# NeuroStimDuino_v2.net
KiCad netlist of a schematic drawn in EAGLE
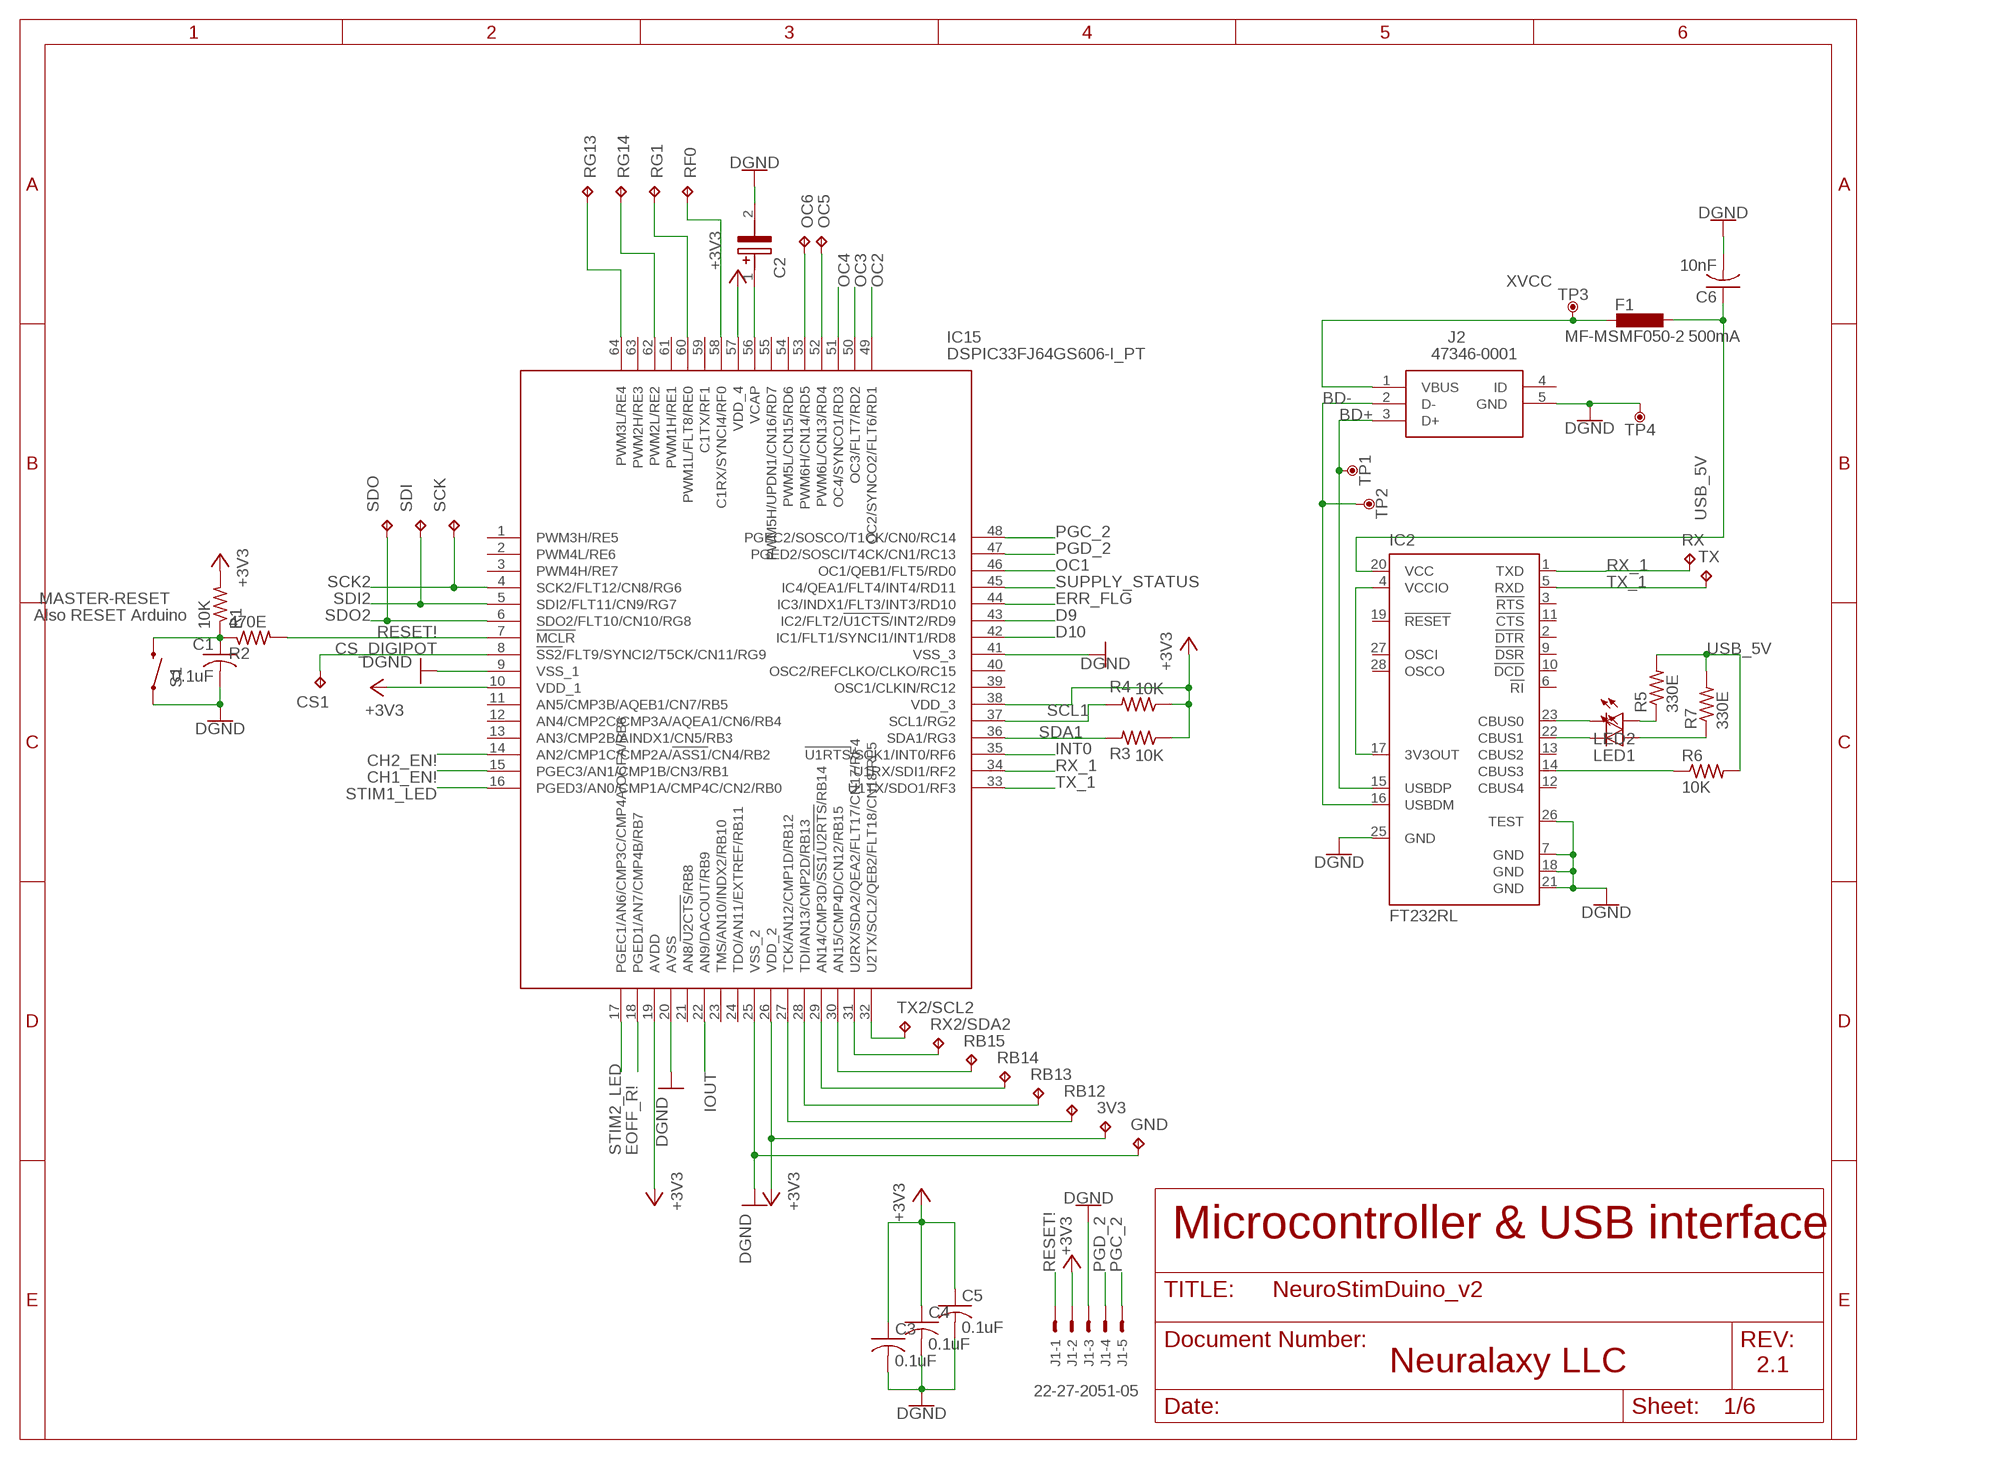
[diagram p0: schematic, sheet 1]
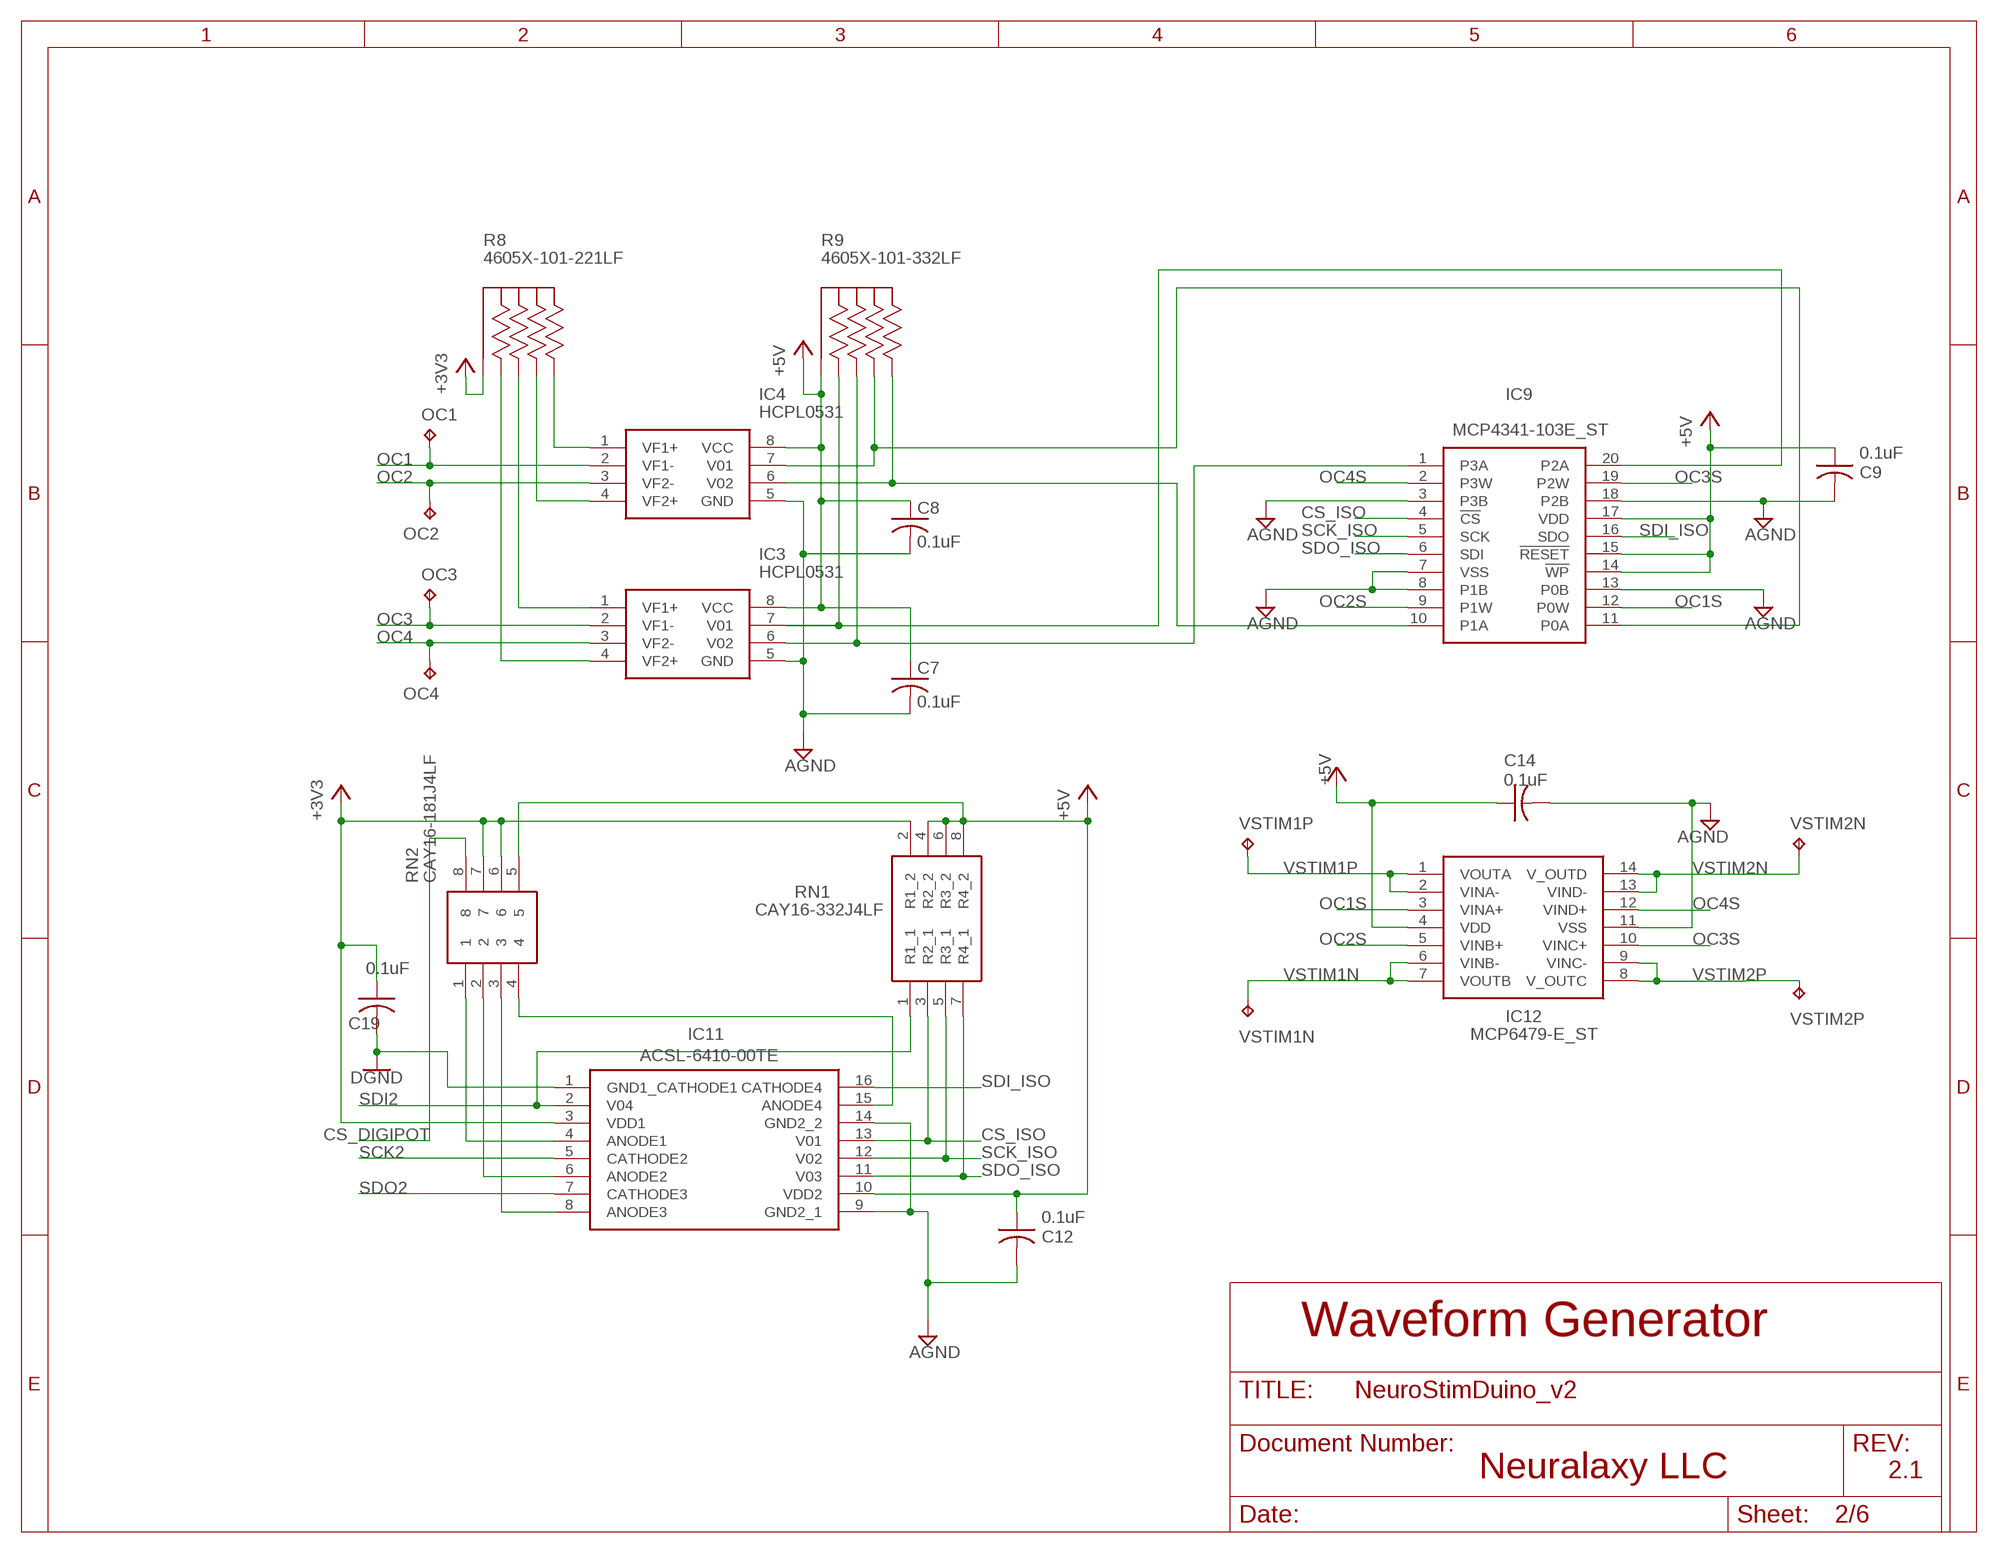
[diagram p1: schematic, sheet 2]
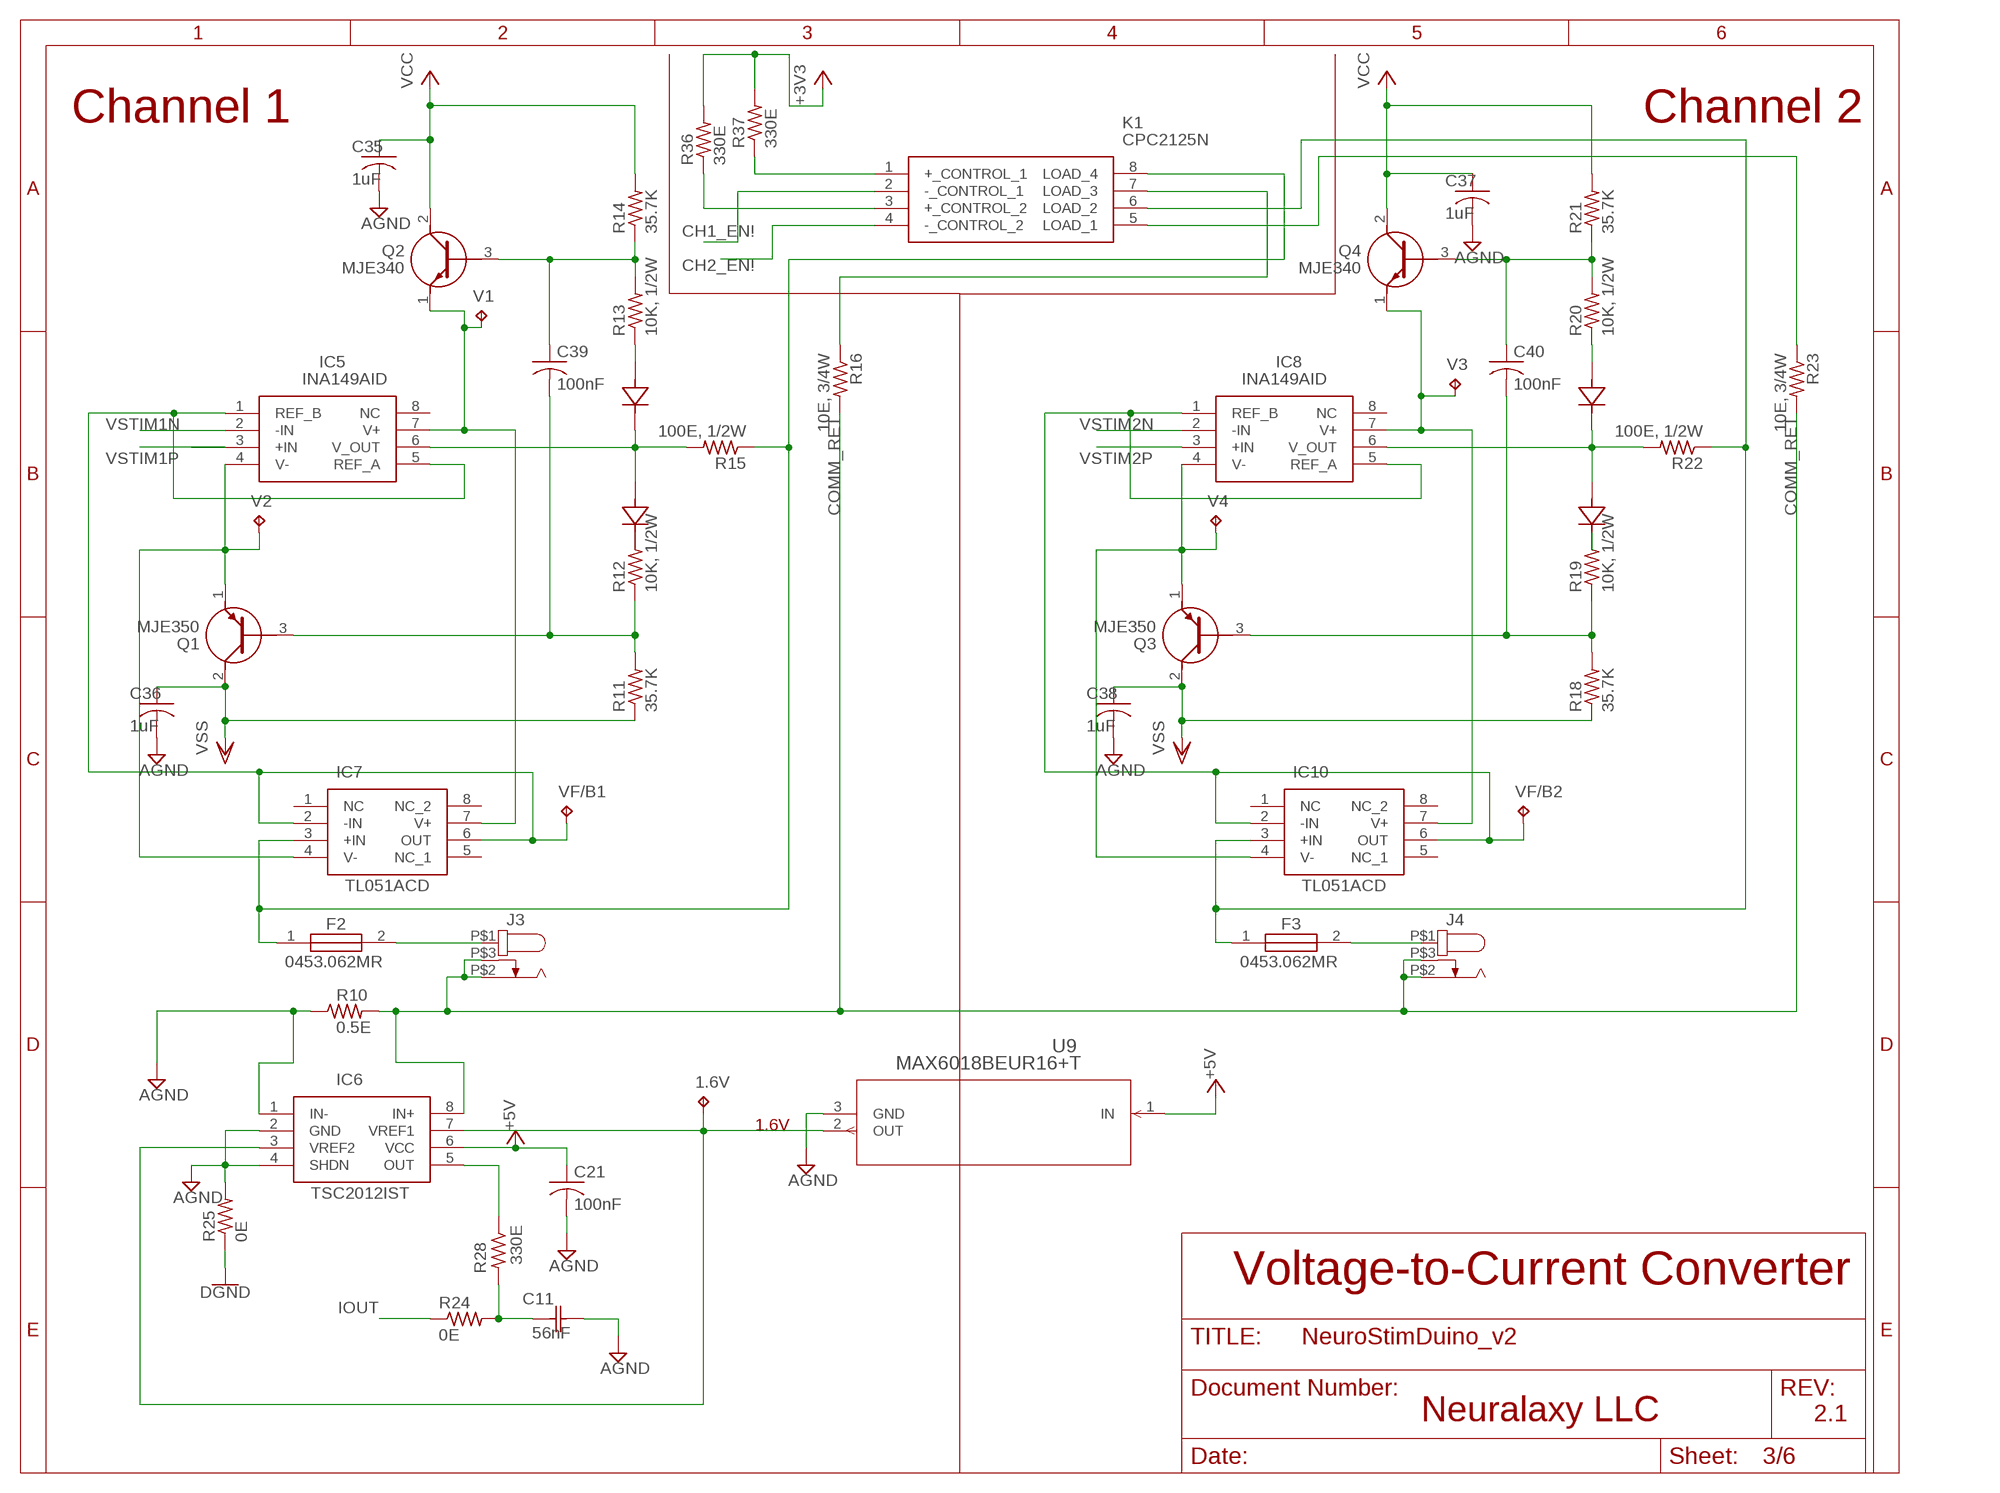
[diagram p2: schematic, sheet 3]
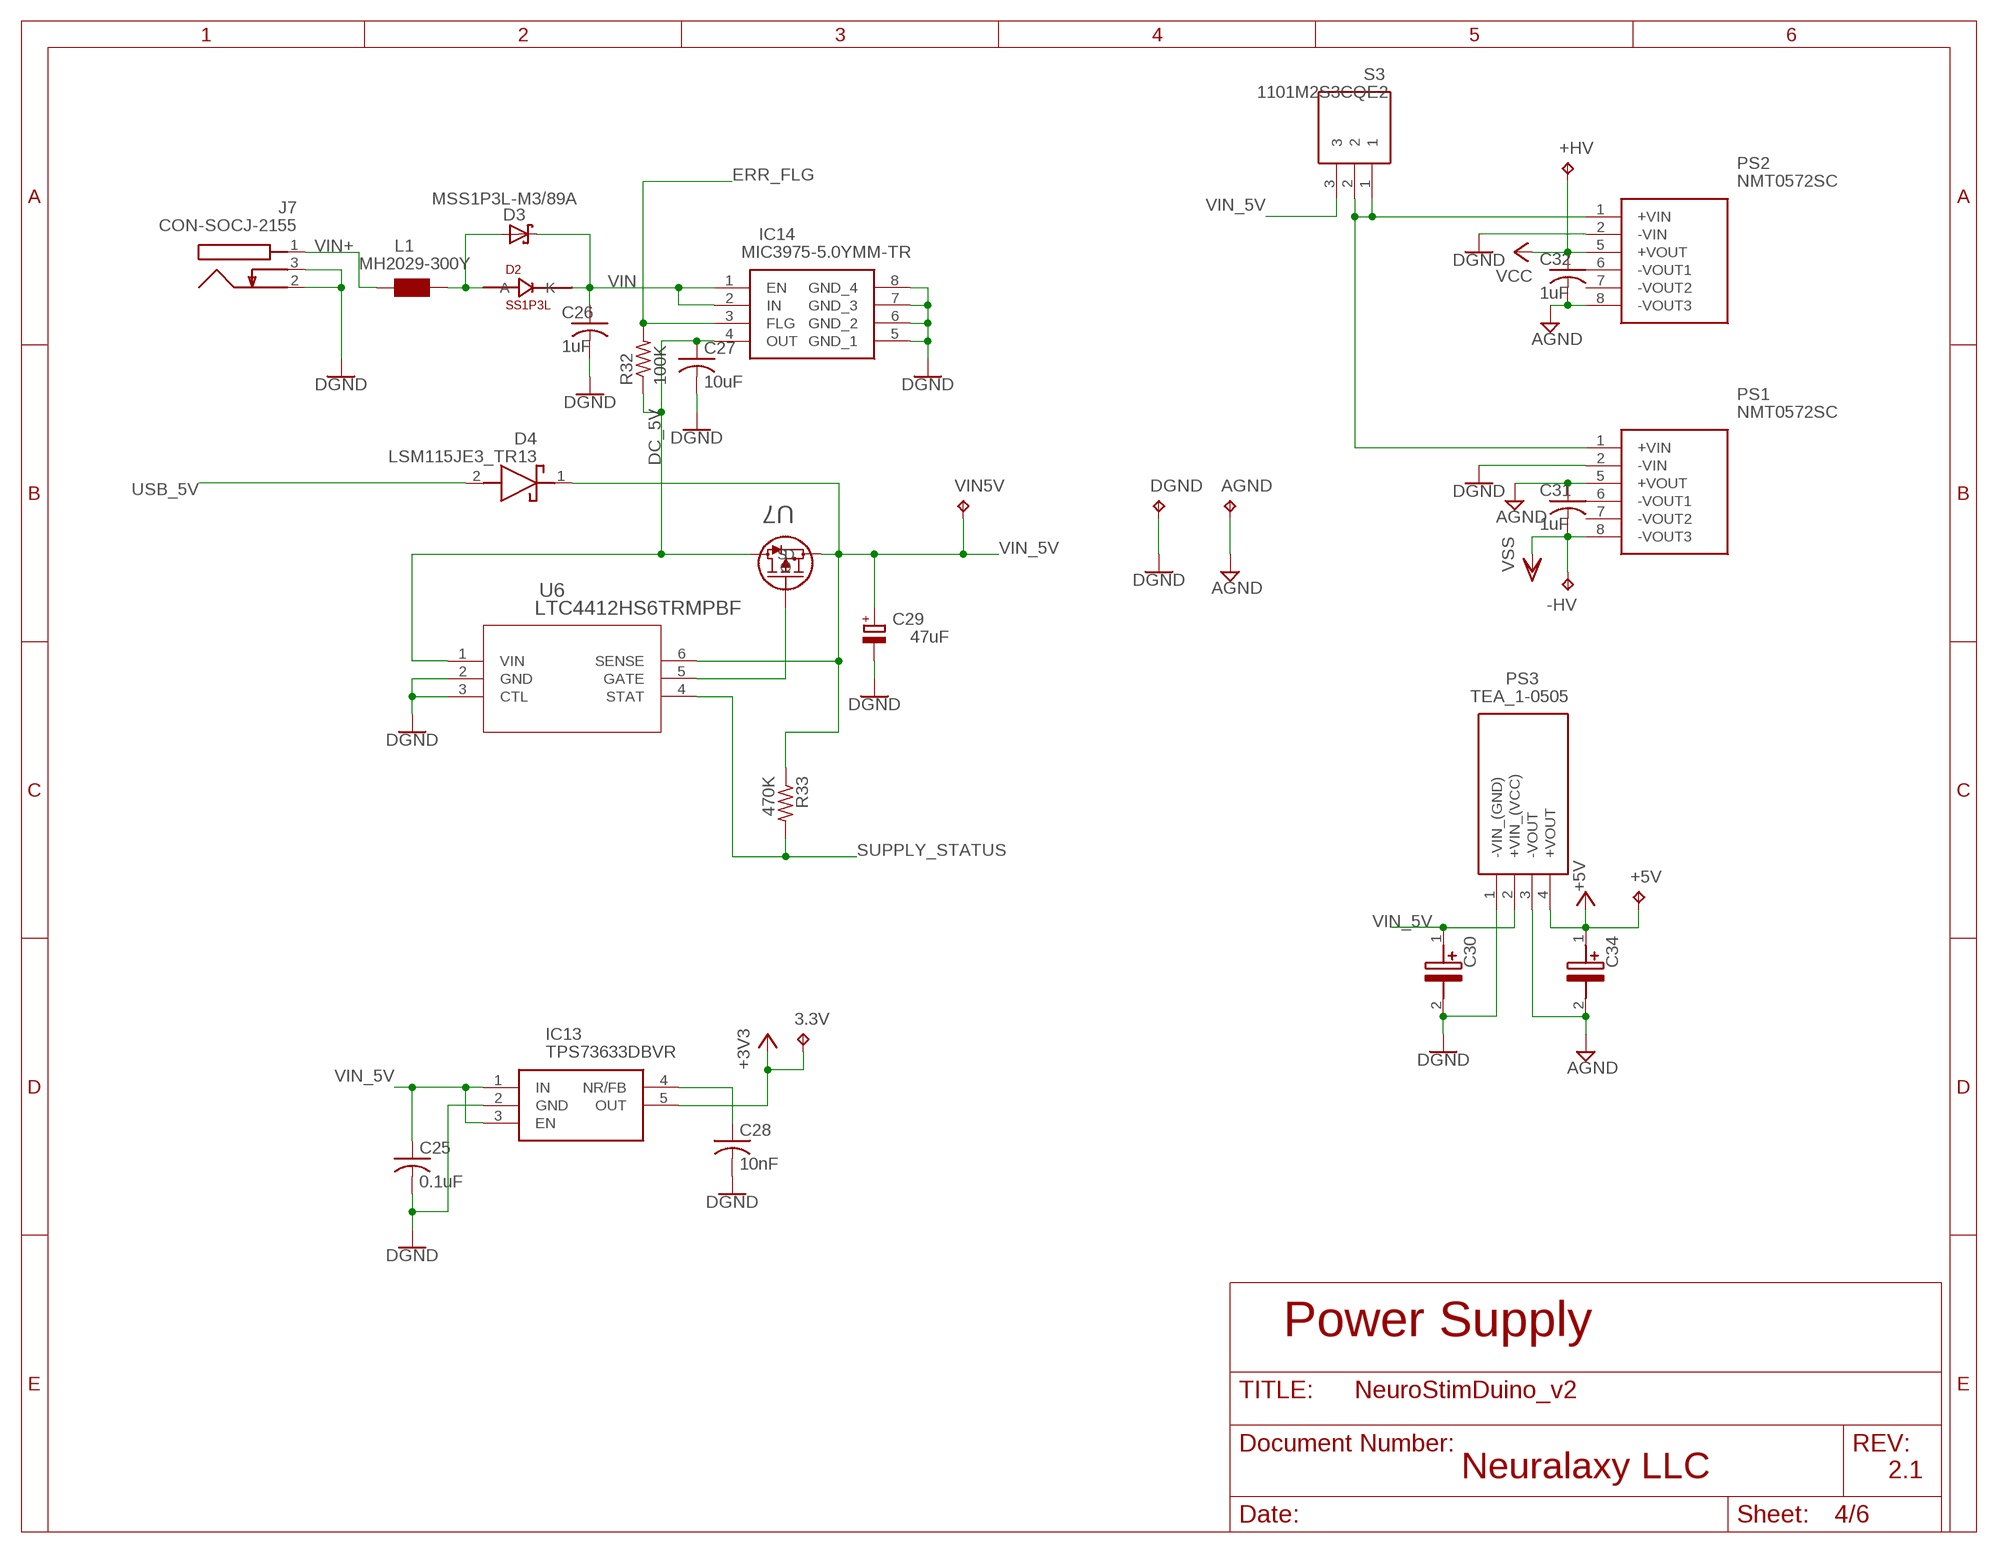
[diagram p3: schematic, sheet 4]
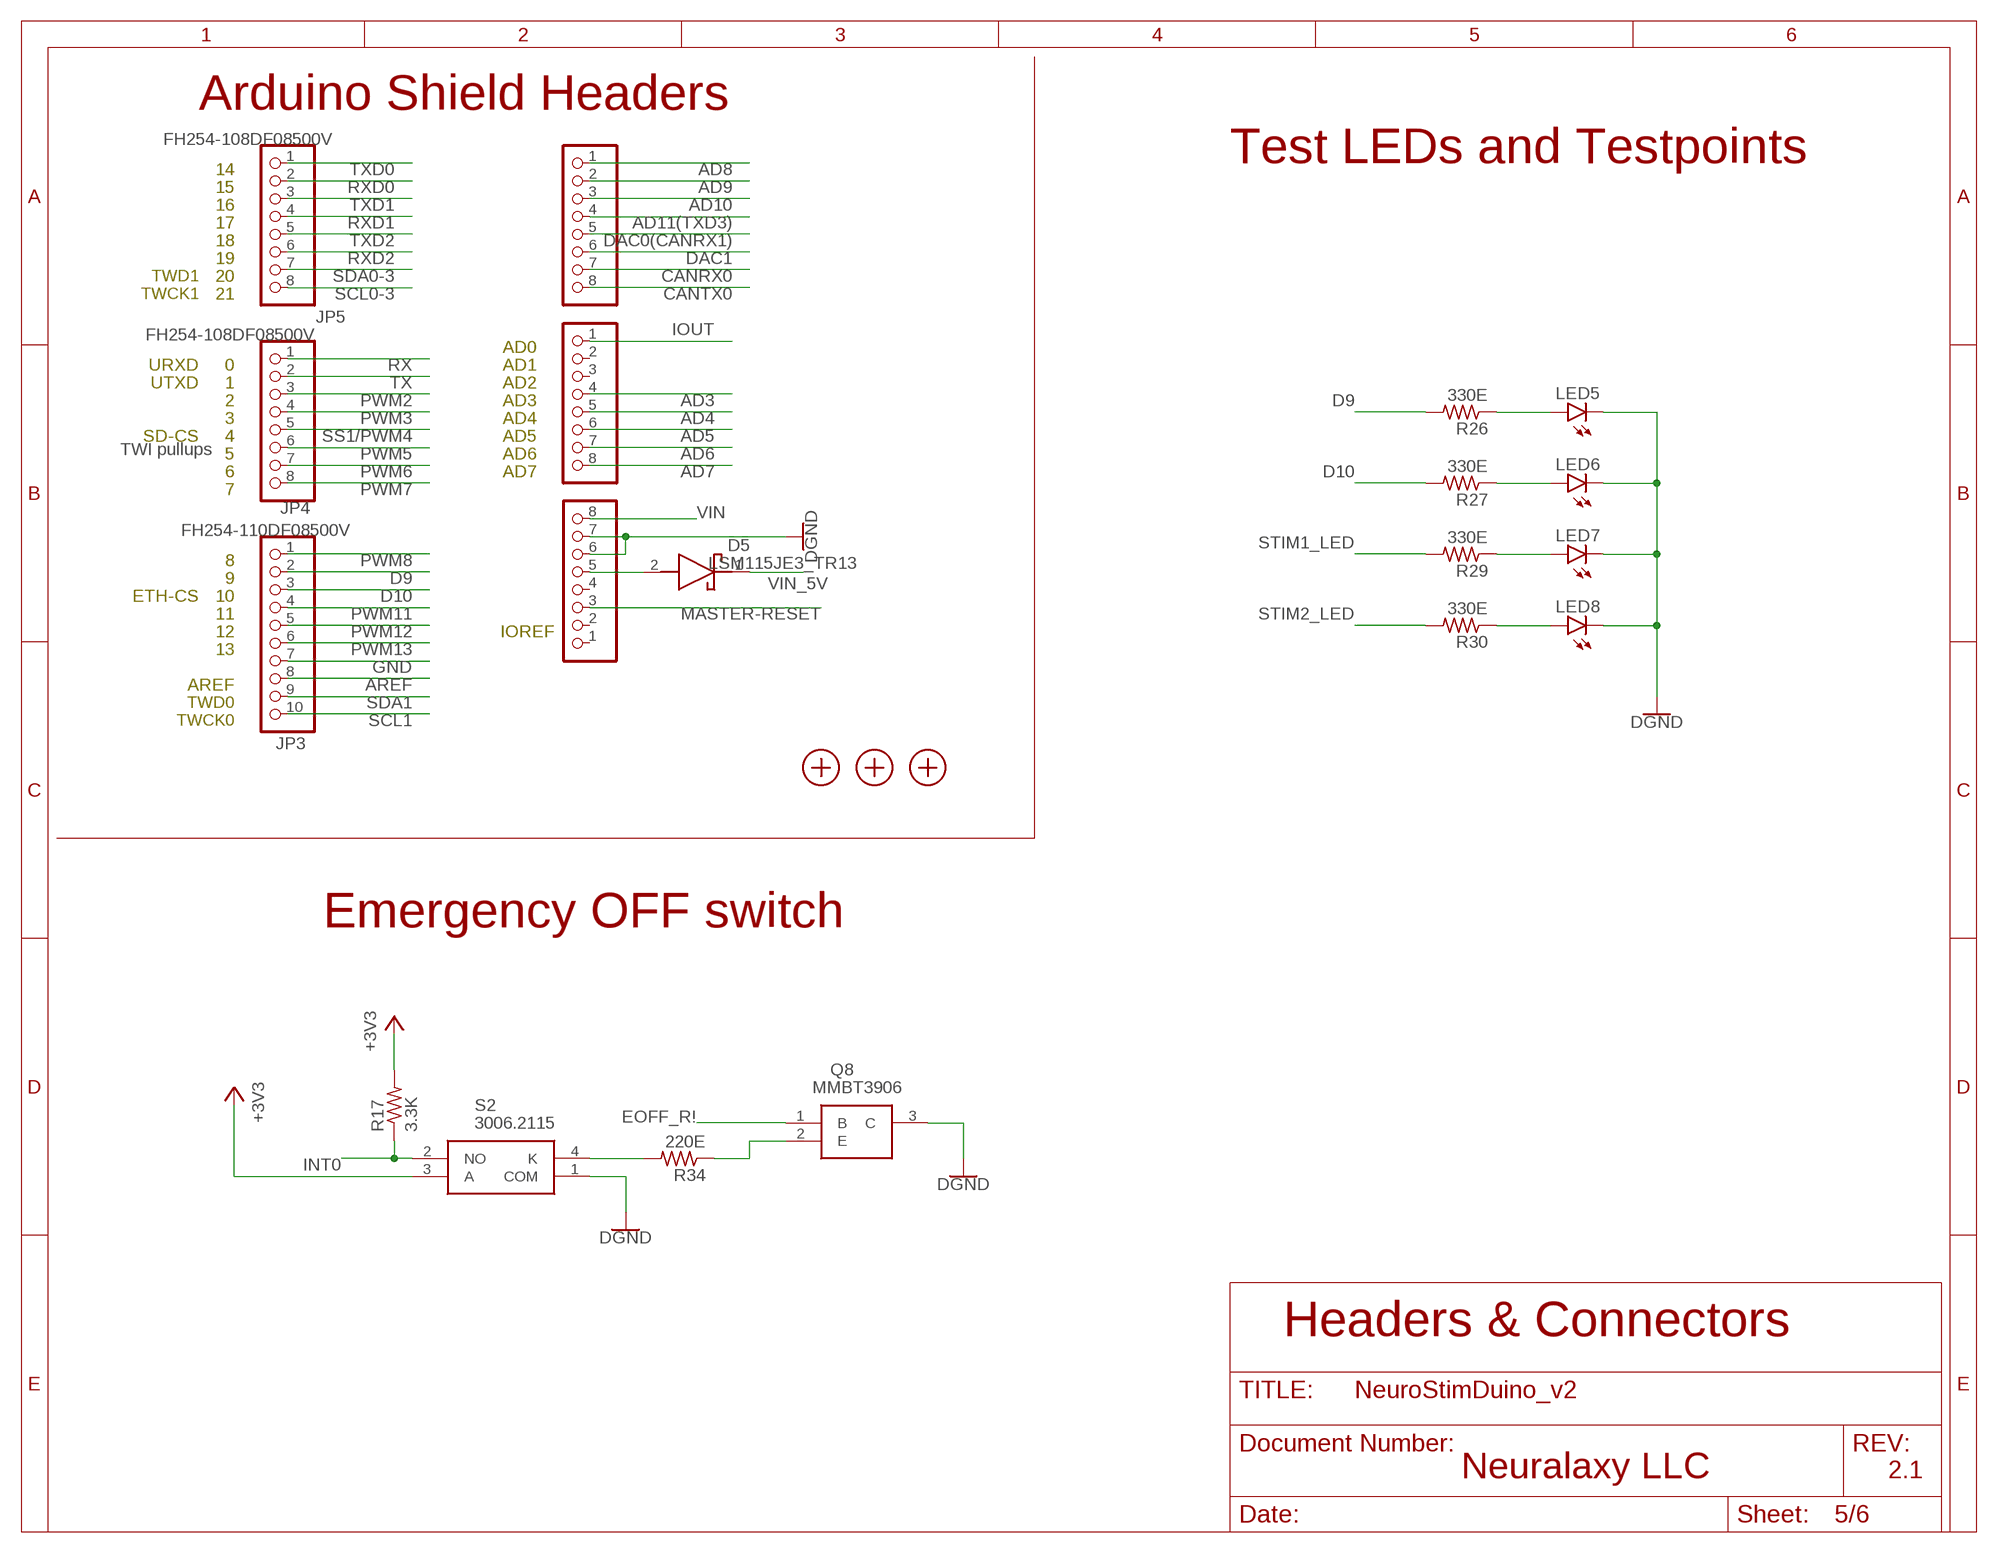
[diagram p4: schematic, sheet 5]
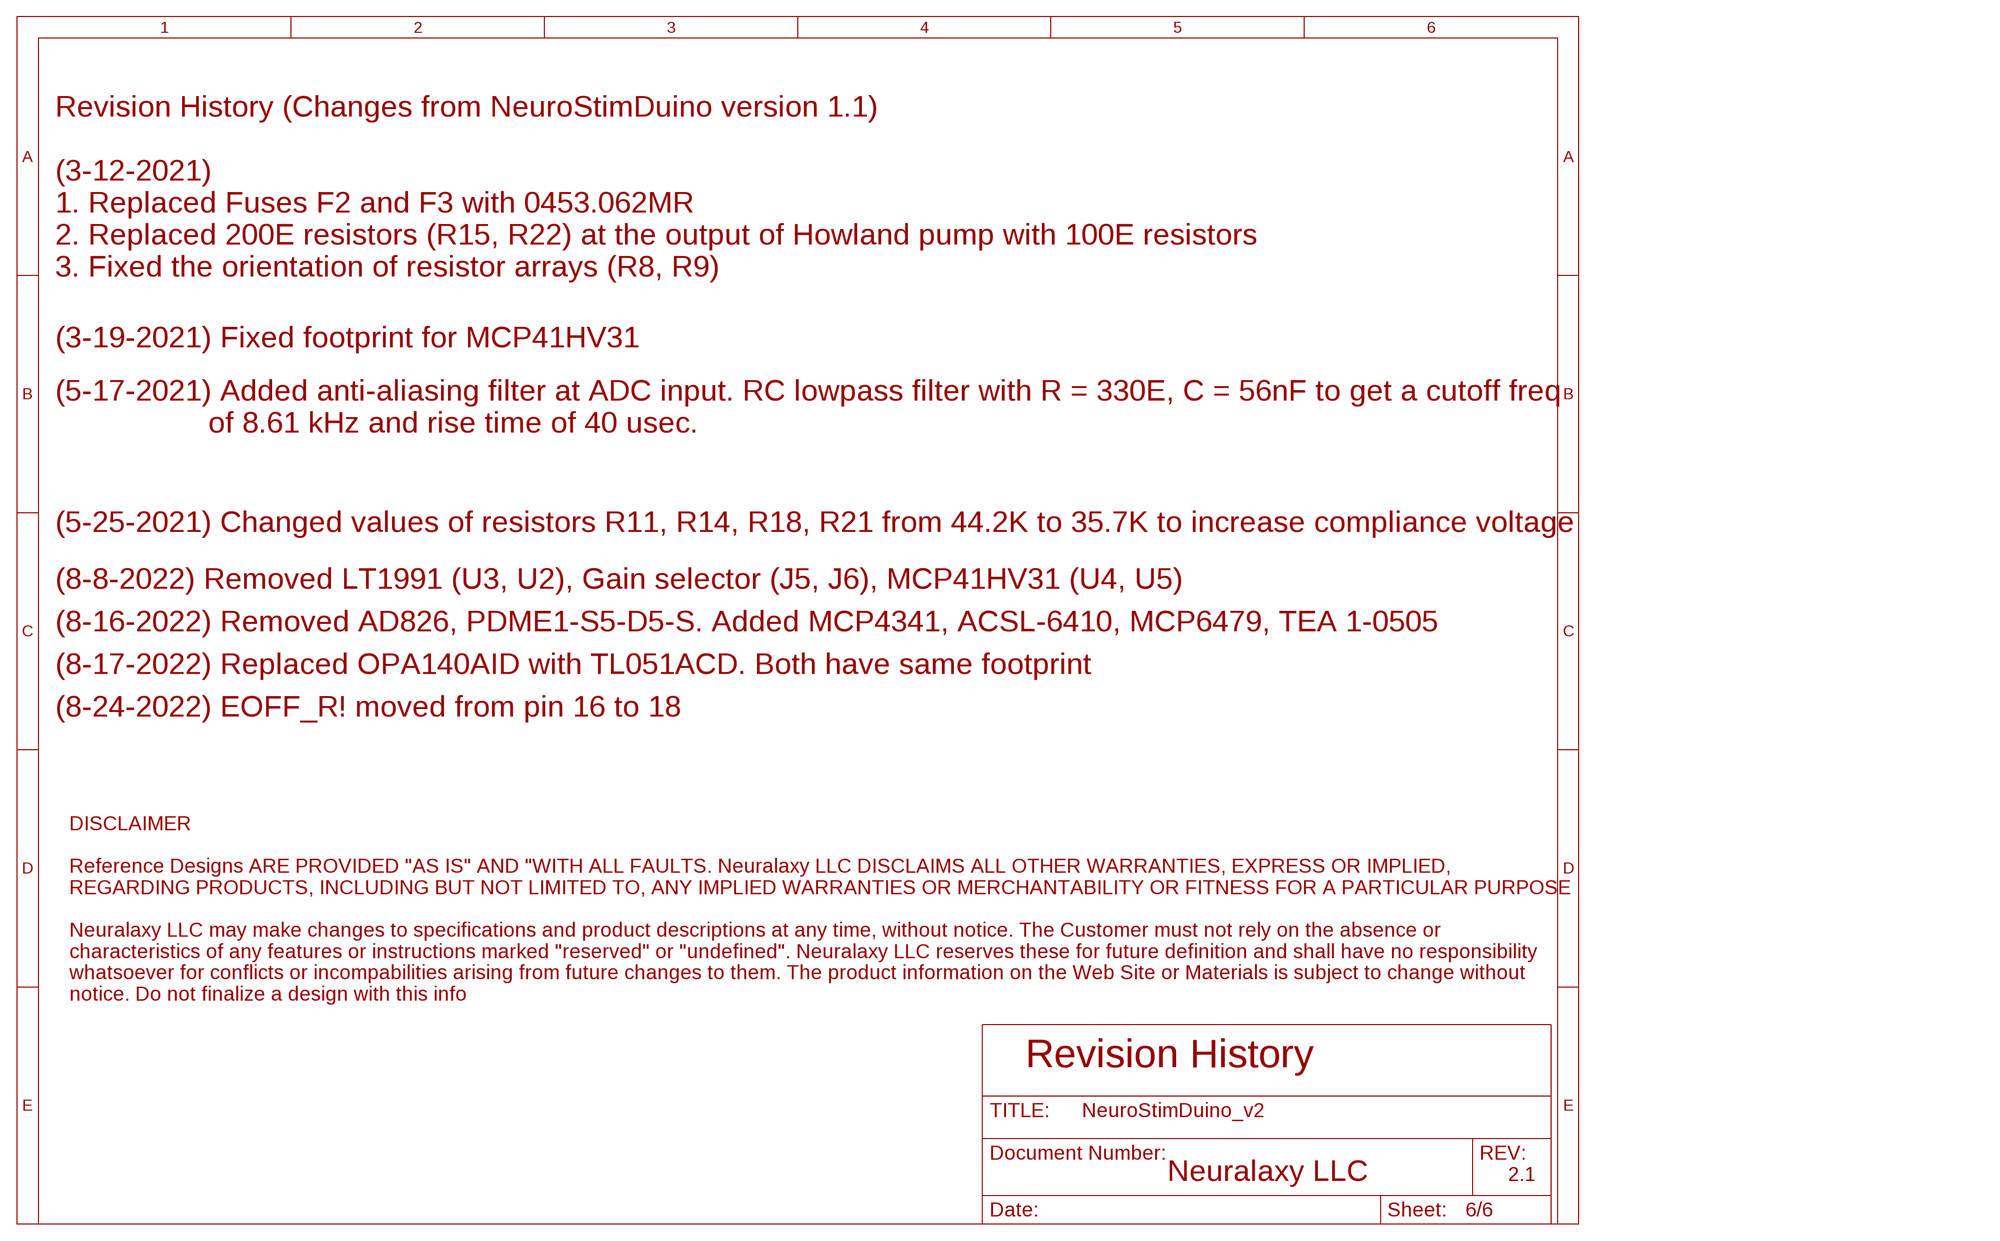
[diagram p5: schematic, sheet 6]

(export (version "E")
  (design (tool "Eeschema 10.0.6"))
  (components
    (comp (ref "3V3")
      (value "TPTP08R")
      (footprint "eagle-import:TP08R")
      (libsource (lib "eagle-import") (part "TPTP08R"))
    )
    (comp (ref "C1")
      (value "0.1uF")
      (footprint "eagle-import:C1206")
      (libsource (lib "eagle-import") (part "C-USC1206"))
    )
    (comp (ref "C2")
      (value "F971C475MAAHT3")
      (footprint "eagle-import:CAPPM3216X180N")
      (fields (field (name "MOUSER_PART_NUMBER") "581-F971C475MAAHT3"))
      (libsource (lib "eagle-import") (part "F971C475MAAHT3"))
    )
    (comp (ref "C3")
      (value "0.1uF")
      (footprint "eagle-import:C1206")
      (libsource (lib "eagle-import") (part "C-USC1206"))
    )
    (comp (ref "C4")
      (value "0.1uF")
      (footprint "eagle-import:C1206")
      (libsource (lib "eagle-import") (part "C-USC1206"))
    )
    (comp (ref "C5")
      (value "0.1uF")
      (footprint "eagle-import:C1206")
      (libsource (lib "eagle-import") (part "C-USC1206"))
    )
    (comp (ref "C6")
      (value "10nF")
      (footprint "eagle-import:C1206")
      (libsource (lib "eagle-import") (part "rcl_334_C-USC1206"))
    )
    (comp (ref "CS1")
      (value "TPTP08R")
      (footprint "eagle-import:TP08R")
      (libsource (lib "eagle-import") (part "TPTP08R"))
    )
    (comp (ref "F1")
      (value "MF-MSMF050-2 500mA")
      (footprint "eagle-import:L1812")
      (fields (field (name "PART_NUMBER") "MF-MSMF050-2"))
      (libsource (lib "eagle-import") (part "0002_MF-MSMF050-2"))
    )
    (comp (ref "GND")
      (value "TPTP08R")
      (footprint "eagle-import:TP08R")
      (libsource (lib "eagle-import") (part "TPTP08R"))
    )
    (comp (ref "IC2")
      (value "FT232RL")
      (footprint "eagle-import:SSOP28")
      (libsource (lib "eagle-import") (part "FT232RL"))
    )
    (comp (ref "IC15")
      (value "DSPIC33FJ64GS606-I_PT")
      (footprint "eagle-import:QFP50P1200X1200X120-64N")
      (fields
        (field (name "MANUFACTURER_PART_NUMBER") "DSPIC33FJ64GS606-I/PT")
        (field (name "MOUSER_PART_NUMBER") "579-33FJ64GS606-I/PT")
      )
      (libsource (lib "eagle-import") (part "DSPIC33FJ64GS606-I_PT"))
    )
    (comp (ref "J1")
      (value "22-27-2051-05")
      (footprint "eagle-import:6410-05")
      (fields (field (name "MF") "MOLEX"))
      (libsource (lib "eagle-import") (part "22-?-0527-2051"))
    )
    (comp (ref "J2")
      (value "47346-0001")
      (footprint "eagle-import:47346-0001")
      (fields (field (name "MOUSER_PART_NUMBER") "538-47346-0001"))
      (libsource (lib "eagle-import") (part "47346-0001"))
    )
    (comp (ref "LED1")
      (value "LEDCHIPLED_1206")
      (footprint "eagle-import:CHIPLED_1206")
      (libsource (lib "eagle-import") (part "LEDCHIPLED_1206"))
    )
    (comp (ref "LED2")
      (value "LEDCHIPLED_1206")
      (footprint "eagle-import:CHIPLED_1206")
      (libsource (lib "eagle-import") (part "LEDCHIPLED_1206"))
    )
    (comp (ref "OC5")
      (value "TPTP08R")
      (footprint "eagle-import:TP08R")
      (libsource (lib "eagle-import") (part "TPTP08R"))
    )
    (comp (ref "OC6")
      (value "TPTP08R")
      (footprint "eagle-import:TP08R")
      (libsource (lib "eagle-import") (part "TPTP08R"))
    )
    (comp (ref "R1")
      (value "10K")
      (footprint "eagle-import:R1206")
      (libsource (lib "eagle-import") (part "R-US_R1206"))
    )
    (comp (ref "R2")
      (value "470E")
      (footprint "eagle-import:R1206")
      (libsource (lib "eagle-import") (part "R-US_R1206"))
    )
    (comp (ref "R3")
      (value "10K")
      (footprint "eagle-import:R1206")
      (libsource (lib "eagle-import") (part "R-US_R1206"))
    )
    (comp (ref "R4")
      (value "10K")
      (footprint "eagle-import:R1206")
      (libsource (lib "eagle-import") (part "R-US_R1206"))
    )
    (comp (ref "R5")
      (value "330E")
      (footprint "eagle-import:R1206")
      (libsource (lib "eagle-import") (part "R-US_R1206"))
    )
    (comp (ref "R6")
      (value "10K")
      (footprint "eagle-import:R1206")
      (libsource (lib "eagle-import") (part "R-US_R1206"))
    )
    (comp (ref "R7")
      (value "330E")
      (footprint "eagle-import:R1206")
      (libsource (lib "eagle-import") (part "R-US_R1206"))
    )
    (comp (ref "RB12")
      (value "TPTP08R")
      (footprint "eagle-import:TP08R")
      (libsource (lib "eagle-import") (part "TPTP08R"))
    )
    (comp (ref "RB13")
      (value "TPTP08R")
      (footprint "eagle-import:TP08R")
      (libsource (lib "eagle-import") (part "TPTP08R"))
    )
    (comp (ref "RB14")
      (value "TPTP08R")
      (footprint "eagle-import:TP08R")
      (libsource (lib "eagle-import") (part "TPTP08R"))
    )
    (comp (ref "RB15")
      (value "TPTP08R")
      (footprint "eagle-import:TP08R")
      (libsource (lib "eagle-import") (part "TPTP08R"))
    )
    (comp (ref "RF0")
      (value "TPTP08R")
      (footprint "eagle-import:TP08R")
      (libsource (lib "eagle-import") (part "TPTP08R"))
    )
    (comp (ref "RG1")
      (value "TPTP08R")
      (footprint "eagle-import:TP08R")
      (libsource (lib "eagle-import") (part "TPTP08R"))
    )
    (comp (ref "RG13")
      (value "TPTP08R")
      (footprint "eagle-import:TP08R")
      (libsource (lib "eagle-import") (part "TPTP08R"))
    )
    (comp (ref "RG14")
      (value "TPTP08R")
      (footprint "eagle-import:TP08R")
      (libsource (lib "eagle-import") (part "TPTP08R"))
    )
    (comp (ref "RX")
      (value "TPTP20R")
      (footprint "eagle-import:TP20R")
      (libsource (lib "eagle-import") (part "TPTP20R"))
    )
    (comp (ref "RX2/SDA2")
      (value "TPTP08R")
      (footprint "eagle-import:TP08R")
      (libsource (lib "eagle-import") (part "TPTP08R"))
    )
    (comp (ref "S1")
      (value "SWITCH-MOMENTARY-2SMD")
      (footprint "eagle-import:TACTILE_SWITCH_SMD")
      (libsource (lib "eagle-import") (part "SWITCH-MOMENTARY-2SMD"))
    )
    (comp (ref "SCK")
      (value "TPTP10R")
      (footprint "eagle-import:TP10R")
      (libsource (lib "eagle-import") (part "TPTP10R"))
    )
    (comp (ref "SDI")
      (value "TPTP10R")
      (footprint "eagle-import:TP10R")
      (libsource (lib "eagle-import") (part "TPTP10R"))
    )
    (comp (ref "SDO")
      (value "TPTP10R")
      (footprint "eagle-import:TP10R")
      (libsource (lib "eagle-import") (part "TPTP10R"))
    )
    (comp (ref "TP1")
      (value "DNP")
      (footprint "eagle-import:TP-1.00MM")
      (libsource (lib "eagle-import") (part "TPTP-1.00MM"))
    )
    (comp (ref "TP2")
      (value "DNP")
      (footprint "eagle-import:TP-1.00MM")
      (libsource (lib "eagle-import") (part "TPTP-1.00MM"))
    )
    (comp (ref "TP3")
      (value "DNP")
      (footprint "eagle-import:TP-1.00MM")
      (libsource (lib "eagle-import") (part "TPTP-1.00MM"))
    )
    (comp (ref "TP4")
      (value "DNP")
      (footprint "eagle-import:TP-1.00MM")
      (libsource (lib "eagle-import") (part "TPTP-1.00MM"))
    )
    (comp (ref "TX")
      (value "TPTP20R")
      (footprint "eagle-import:TP20R")
      (libsource (lib "eagle-import") (part "TPTP20R"))
    )
    (comp (ref "TX2/SCL2")
      (value "TPTP08R")
      (footprint "eagle-import:TP08R")
      (libsource (lib "eagle-import") (part "TPTP08R"))
    )
    (comp (ref "C7")
      (value "0.1uF")
      (footprint "eagle-import:C1206")
      (libsource (lib "eagle-import") (part "rcl_334_C-USC1206"))
    )
    (comp (ref "C8")
      (value "0.1uF")
      (footprint "eagle-import:C1206")
      (libsource (lib "eagle-import") (part "rcl_334_C-USC1206"))
    )
    (comp (ref "C9")
      (value "0.1uF")
      (footprint "eagle-import:C1206")
      (libsource (lib "eagle-import") (part "rcl_334_C-USC1206"))
    )
    (comp (ref "C12")
      (value "0.1uF")
      (footprint "eagle-import:C1206")
      (libsource (lib "eagle-import") (part "rcl_334_C-USC1206"))
    )
    (comp (ref "C14")
      (value "0.1uF")
      (footprint "eagle-import:C1206")
      (libsource (lib "eagle-import") (part "rcl_334_C-USC1206"))
    )
    (comp (ref "C19")
      (value "0.1uF")
      (footprint "eagle-import:C1206")
      (libsource (lib "eagle-import") (part "rcl_334_C-USC1206"))
    )
    (comp (ref "IC3")
      (value "HCPL0531")
      (footprint "eagle-import:SOIC127P594X363-8N")
      (fields (field (name "MOUSER_PART_NUMBER") "512-HCPL0531"))
      (libsource (lib "eagle-import") (part "HCPL0531"))
    )
    (comp (ref "IC4")
      (value "HCPL0531")
      (footprint "eagle-import:SOIC127P594X363-8N")
      (fields (field (name "MOUSER_PART_NUMBER") "512-HCPL0531"))
      (libsource (lib "eagle-import") (part "HCPL0531"))
    )
    (comp (ref "IC9")
      (value "MCP4341-103E_ST")
      (footprint "eagle-import:SOP65P640X120-20N")
      (fields
        (field (name "MANUFACTURER_PART_NUMBER") "MCP4341-103E/ST")
        (field (name "MOUSER_PART_NUMBER") "579-MCP4341103E/ST")
      )
      (libsource (lib "eagle-import") (part "MCP4341-103E_ST"))
    )
    (comp (ref "IC11")
      (value "ACSL-6410-00TE")
      (footprint "eagle-import:SOIC127P599X152-16N")
      (fields (field (name "MOUSER_PART_NUMBER") "630-ACSL-6410-00TE"))
      (libsource (lib "eagle-import") (part "ACSL-6410-00TE"))
    )
    (comp (ref "IC12")
      (value "MCP6479-E_ST")
      (footprint "eagle-import:SOP65P640X120-14N")
      (fields
        (field (name "MANUFACTURER_PART_NUMBER") "MCP6479-E/ST")
        (field (name "MOUSER_PART_NUMBER") "579-MCP6479-E/ST")
      )
      (libsource (lib "eagle-import") (part "MCP6479-E_ST"))
    )
    (comp (ref "OC1")
      (value "TPTP08R")
      (footprint "eagle-import:TP08R")
      (libsource (lib "eagle-import") (part "TPTP08R"))
    )
    (comp (ref "OC2")
      (value "TPTP08R")
      (footprint "eagle-import:TP08R")
      (libsource (lib "eagle-import") (part "TPTP08R"))
    )
    (comp (ref "OC3")
      (value "TPTP10R")
      (footprint "eagle-import:TP10R")
      (libsource (lib "eagle-import") (part "TPTP10R"))
    )
    (comp (ref "OC4")
      (value "TPTP10R")
      (footprint "eagle-import:TP10R")
      (libsource (lib "eagle-import") (part "TPTP10R"))
    )
    (comp (ref "R8")
      (value "4605X-101-221LF")
      (footprint "eagle-import:BO_4605X")
      (fields (field (name "MANUFACTURER_PART_NUMBER") "4605X-101-222LF"))
      (libsource (lib "eagle-import") (part "4605X-101-221LF"))
    )
    (comp (ref "R9")
      (value "4605X-101-332LF")
      (footprint "eagle-import:BO_4605X")
      (fields (field (name "MANUFACTURER_PART_NUMBER") "4605X-101-222LF"))
      (libsource (lib "eagle-import") (part "4605X-101-332LF"))
    )
    (comp (ref "RN1")
      (value "CAY16-332J4LF")
      (footprint "eagle-import:CAY16-J4")
      (fields (field (name "MOUSER_PART_NUMBER") "652-CAY16-332J4LF"))
      (libsource (lib "eagle-import") (part "CAY16-332J4LF"))
    )
    (comp (ref "RN2")
      (value "CAY16-181J4LF")
      (footprint "eagle-import:CAY16181J4LF")
      (fields (field (name "MOUSER_PART_NUMBER") "652-CAY16-181J4LF"))
      (libsource (lib "eagle-import") (part "CAY16-181J4LF"))
    )
    (comp (ref "VSTIM1N")
      (value "TPTP08R")
      (footprint "eagle-import:TP08R")
      (libsource (lib "eagle-import") (part "TPTP08R"))
    )
    (comp (ref "VSTIM1P")
      (value "TPTP08R")
      (footprint "eagle-import:TP08R")
      (libsource (lib "eagle-import") (part "TPTP08R"))
    )
    (comp (ref "VSTIM2N")
      (value "TPTP08R")
      (footprint "eagle-import:TP08R")
      (libsource (lib "eagle-import") (part "TPTP08R"))
    )
    (comp (ref "VSTIM2P")
      (value "TPTP08R")
      (footprint "eagle-import:TP08R")
      (libsource (lib "eagle-import") (part "TPTP08R"))
    )
    (comp (ref "D5")
      (value "LSM115JE3_TR13")
      (footprint "eagle-import:DIOM5436X330N")
      (fields
        (field (name "ARROW_PART_NUMBER") "LSM115JE3/TR13")
        (field (name "MOUSER_PART_NUMBER") "494-LSM115JE3/TR13")
      )
      (libsource (lib "eagle-import") (part "LSM115JE3_TR13"))
    )
    (comp (ref "JP3")
      (value "FH254-110DF08500V")
      (footprint "eagle-import:1X10")
      (fields (field (name "PART_NUMBER") "20TW-537"))
      (libsource (lib "eagle-import") (part "1684_20TW-537"))
    )
    (comp (ref "JP4")
      (value "FH254-108DF08500V")
      (footprint "eagle-import:1X08")
      (fields (field (name "PART_NUMBER") "20TW-536"))
      (libsource (lib "eagle-import") (part "1683_20TW-536"))
    )
    (comp (ref "JP5")
      (value "FH254-108DF08500V")
      (footprint "eagle-import:1X08")
      (fields (field (name "PART_NUMBER") "20TW-536"))
      (libsource (lib "eagle-import") (part "1683_20TW-536"))
    )
    (comp (ref "JP6")
      (value "FH254-108DF08500V")
      (footprint "eagle-import:1X08")
      (fields (field (name "PART_NUMBER") "20TW-536"))
      (libsource (lib "eagle-import") (part "1683_20TW-536"))
    )
    (comp (ref "JP7")
      (value "FH254-108DF08500V")
      (footprint "eagle-import:1X08")
      (fields (field (name "PART_NUMBER") "20TW-536"))
      (libsource (lib "eagle-import") (part "1683_20TW-536"))
    )
    (comp (ref "JP8")
      (value "FH254-108DF08500V")
      (footprint "eagle-import:1X08")
      (fields (field (name "PART_NUMBER") "20TW-536"))
      (libsource (lib "eagle-import") (part "1683_20TW-536"))
    )
    (comp (ref "LED5")
      (value "LEDCHIPLED_1206")
      (footprint "eagle-import:CHIPLED_1206")
      (libsource (lib "eagle-import") (part "LEDCHIPLED_1206"))
    )
    (comp (ref "LED6")
      (value "LEDCHIPLED_1206")
      (footprint "eagle-import:CHIPLED_1206")
      (libsource (lib "eagle-import") (part "LEDCHIPLED_1206"))
    )
    (comp (ref "LED7")
      (value "LEDCHIPLED_1206")
      (footprint "eagle-import:CHIPLED_1206")
      (libsource (lib "eagle-import") (part "LEDCHIPLED_1206"))
    )
    (comp (ref "LED8")
      (value "LEDCHIPLED_1206")
      (footprint "eagle-import:CHIPLED_1206")
      (libsource (lib "eagle-import") (part "LEDCHIPLED_1206"))
    )
    (comp (ref "Q8")
      (value "MMBT3906")
      (footprint "eagle-import:SOT95P240X120-3N")
      (fields (field (name "MOUSER_PART_NUMBER") "512-MMBT3906"))
      (libsource (lib "eagle-import") (part "MMBT3906"))
    )
    (comp (ref "R17")
      (value "3.3K")
      (footprint "eagle-import:R1206")
      (libsource (lib "eagle-import") (part "rcl_334_R-US_R1206"))
    )
    (comp (ref "R26")
      (value "330E")
      (footprint "eagle-import:R0603")
      (libsource (lib "eagle-import") (part "R-US_R0603"))
    )
    (comp (ref "R27")
      (value "330E")
      (footprint "eagle-import:R0603")
      (libsource (lib "eagle-import") (part "R-US_R0603"))
    )
    (comp (ref "R29")
      (value "330E")
      (footprint "eagle-import:R0603")
      (libsource (lib "eagle-import") (part "R-US_R0603"))
    )
    (comp (ref "R30")
      (value "330E")
      (footprint "eagle-import:R0603")
      (libsource (lib "eagle-import") (part "R-US_R0603"))
    )
    (comp (ref "R34")
      (value "220E")
      (footprint "eagle-import:R1206")
      (libsource (lib "eagle-import") (part "rcl_334_R-US_R1206"))
    )
    (comp (ref "S2")
      (value "3006.2115")
      (footprint "eagle-import:30062115")
      (fields (field (name "MOUSER_PART_NUMBER") "979-3006.2115"))
      (libsource (lib "eagle-import") (part "3006.2115"))
    )
    (comp (ref "U$1")
      (value "FIDUCIALMOUNT")
      (footprint "eagle-import:FIDUCIA-MOUNT")
      (libsource (lib "eagle-import") (part "FIDUCIALMOUNT"))
    )
    (comp (ref "U$2")
      (value "FIDUCIALMOUNT")
      (footprint "eagle-import:FIDUCIA-MOUNT")
      (libsource (lib "eagle-import") (part "FIDUCIALMOUNT"))
    )
    (comp (ref "U$3")
      (value "FIDUCIALMOUNT")
      (footprint "eagle-import:FIDUCIA-MOUNT")
      (libsource (lib "eagle-import") (part "FIDUCIALMOUNT"))
    )
    (comp (ref "+5V")
      (value "TPTP10R")
      (footprint "eagle-import:TP10R")
      (libsource (lib "eagle-import") (part "TPTP10R"))
    )
    (comp (ref "+HV")
      (value "TPTP10R")
      (footprint "eagle-import:TP10R")
      (libsource (lib "eagle-import") (part "TPTP10R"))
    )
    (comp (ref "-HV")
      (value "TPTP10R")
      (footprint "eagle-import:TP10R")
      (libsource (lib "eagle-import") (part "TPTP10R"))
    )
    (comp (ref "3.3V")
      (value "TPTP10R")
      (footprint "eagle-import:TP10R")
      (libsource (lib "eagle-import") (part "TPTP10R"))
    )
    (comp (ref "AGND")
      (value "TPTP10R")
      (footprint "eagle-import:TP10R")
      (libsource (lib "eagle-import") (part "TPTP10R"))
    )
    (comp (ref "C25")
      (value "0.1uF")
      (footprint "eagle-import:C1206")
      (libsource (lib "eagle-import") (part "C-USC1206"))
    )
    (comp (ref "C26")
      (value "1uF")
      (footprint "eagle-import:C0805")
      (libsource (lib "eagle-import") (part "rcl_334_C-USC0805"))
    )
    (comp (ref "C27")
      (value "10uF")
      (footprint "eagle-import:C0805")
      (libsource (lib "eagle-import") (part "rcl_334_C-USC0805"))
    )
    (comp (ref "C28")
      (value "10nF")
      (footprint "eagle-import:C1206")
      (libsource (lib "eagle-import") (part "C-USC1206"))
    )
    (comp (ref "C29")
      (value "47uF")
      (footprint "eagle-import:PANASONIC_D")
      (libsource (lib "eagle-import") (part "0113_47UF"))
    )
    (comp (ref "C30")
      (value "4.7uF")
      (footprint "eagle-import:CAPPM7343X310N")
      (fields
        (field (name "MANUFACTURER_PART_NUMBER") "593D475X9050D2TE3")
        (field (name "MOUSER_PART_NUMBER") "74-593D475X9050D2TE3")
      )
      (libsource (lib "eagle-import") (part "593D475X9050D2TE3"))
    )
    (comp (ref "C31")
      (value "1uF")
      (footprint "eagle-import:C0805")
      (libsource (lib "eagle-import") (part "rcl_334_C-USC0805"))
    )
    (comp (ref "C32")
      (value "1uF")
      (footprint "eagle-import:C0805")
      (libsource (lib "eagle-import") (part "rcl_334_C-USC0805"))
    )
    (comp (ref "C34")
      (value "4.7uF")
      (footprint "eagle-import:CAPPM7343X310N")
      (fields
        (field (name "MANUFACTURER_PART_NUMBER") "593D475X9050D2TE3")
        (field (name "MOUSER_PART_NUMBER") "74-593D475X9050D2TE3")
      )
      (libsource (lib "eagle-import") (part "593D475X9050D2TE3"))
    )
    (comp (ref "D2")
      (value "SS1P3L")
      (footprint "eagle-import:DO220AAL")
      (fields (field (name "PART_NUMBER") "SS1P3L-M3/84A"))
      (libsource (lib "eagle-import") (part "0025_SS1P3L-M3/84A"))
    )
    (comp (ref "D3")
      (value "MSS1P3L-M3/89A")
      (footprint "eagle-import:MICROSMP")
      (libsource (lib "eagle-import") (part "1653_MSS1P3L-M3/89A"))
    )
    (comp (ref "D4")
      (value "LSM115JE3_TR13")
      (footprint "eagle-import:DIOM5436X330N")
      (fields
        (field (name "ARROW_PART_NUMBER") "LSM115JE3/TR13")
        (field (name "MOUSER_PART_NUMBER") "494-LSM115JE3/TR13")
      )
      (libsource (lib "eagle-import") (part "LSM115JE3_TR13"))
    )
    (comp (ref "DGND")
      (value "TPTP10R")
      (footprint "eagle-import:TP10R")
      (libsource (lib "eagle-import") (part "TPTP10R"))
    )
    (comp (ref "IC13")
      (value "TPS73633DBVR")
      (footprint "eagle-import:SOT95P280X145-5N")
      (fields (field (name "MOUSER_PART_NUMBER") "595-TPS73633DBVR"))
      (libsource (lib "eagle-import") (part "TPS73633DBVR"))
    )
    (comp (ref "IC14")
      (value "MIC3975-5.0YMM-TR")
      (footprint "eagle-import:SOP65P490X109-8N")
      (libsource (lib "eagle-import") (part "MIC3975-5.0YMM-TR"))
    )
    (comp (ref "J7")
      (value "CON-SOCJ-2155")
      (footprint "eagle-import:CONSOCJ2155")
      (fields (field (name "MOUSER_PART_NUMBER") "992-CON-SOCJ-2155"))
      (libsource (lib "eagle-import") (part "CON-SOCJ-2155"))
    )
    (comp (ref "L1")
      (value "MH2029-300Y")
      (footprint "eagle-import:0805")
      (fields (field (name "PART_NUMBER") "BLM21PG300SN1D_/_MH2029-300Y"))
      (libsource (lib "eagle-import") (part "0001_BLM21PG300SN1D_/_MH2029-300Y"))
    )
    (comp (ref "PS1")
      (value "NMT0572SC")
      (footprint "eagle-import:NMT1272SC")
      (fields (field (name "MOUSER_PART_NUMBER") "580-NMT0572SC"))
      (libsource (lib "eagle-import") (part "NMT0572SC"))
    )
    (comp (ref "PS2")
      (value "NMT0572SC")
      (footprint "eagle-import:NMT1272SC")
      (fields (field (name "MOUSER_PART_NUMBER") "580-NMT0572SC"))
      (libsource (lib "eagle-import") (part "NMT0572SC"))
    )
    (comp (ref "PS3")
      (value "TEA_1-0505")
      (footprint "eagle-import:TEA10505")
      (fields
        (field (name "MANUFACTURER_PART_NUMBER") "TEA 1-0505")
        (field (name "MOUSER_PART_NUMBER") "495-TEA1-0505")
      )
      (libsource (lib "eagle-import") (part "TEA_1-0505"))
    )
    (comp (ref "R32")
      (value "100K")
      (footprint "eagle-import:R1206")
      (libsource (lib "eagle-import") (part "rcl_334_R-US_R1206"))
    )
    (comp (ref "R33")
      (value "470K")
      (footprint "eagle-import:R1206")
      (libsource (lib "eagle-import") (part "rcl_334_R-US_R1206"))
    )
    (comp (ref "S3")
      (value "1101M2S3CQE2")
      (footprint "eagle-import:1000-SERIES(SPDT)")
      (fields (field (name "MOUSER_PART_NUMBER") "611-1101M2S3CQE2"))
      (libsource (lib "eagle-import") (part "1101M2S3CQE2"))
    )
    (comp (ref "U6")
      (value "LTC4412HS6TRMPBF")
      (footprint "eagle-import:TSOT-23_S6_ADI")
      (fields
        (field (name "MANUFACTURER_PART_NUMBER") "LTC4412HS6#TRMPBF")
        (field (name "COPYRIGHT") "Copyright (C) 2018 Accelerated Designs. All rights reserved")
      )
      (libsource (lib "eagle-import") (part "LTC4412HS6TRMPBF"))
    )
    (comp (ref "U7")
      (value "PMV48XP,215TO-236_SOT23_NEX-L")
      (footprint "eagle-import:TO-236_SOT23_NEX-L")
      (fields
        (field (name "MANUFACTURER_PART_NUMBER") "PMV48XP,215")
        (field (name "COPYRIGHT") "Copyright (C) 2018 Accelerated Designs. All rights reserved")
      )
      (libsource (lib "eagle-import") (part "PMV48XP,215TO-236_SOT23_NEX-L"))
    )
    (comp (ref "VIN5V")
      (value "TPTP10R")
      (footprint "eagle-import:TP10R")
      (libsource (lib "eagle-import") (part "TPTP10R"))
    )
    (comp (ref "1.6V")
      (value "TPTP10R")
      (footprint "eagle-import:TP10R")
      (libsource (lib "eagle-import") (part "TPTP10R"))
    )
    (comp (ref "C11")
      (value "56nF")
      (footprint "eagle-import:CAPC17595_87N_KEM")
      (fields (field (name "MANUFACTURER_PART_NUMBER") "C0603C563J4RACTU"))
      (libsource (lib "eagle-import") (part "C0603C563J4RACTU"))
    )
    (comp (ref "C21")
      (value "100nF")
      (footprint "eagle-import:C1206")
      (libsource (lib "eagle-import") (part "rcl_334_C-USC1206"))
    )
    (comp (ref "C35")
      (value "1uF")
      (footprint "eagle-import:C0805")
      (libsource (lib "eagle-import") (part "rcl_334_C-USC0805"))
    )
    (comp (ref "C36")
      (value "1uF")
      (footprint "eagle-import:C0805")
      (libsource (lib "eagle-import") (part "rcl_334_C-USC0805"))
    )
    (comp (ref "C37")
      (value "1uF")
      (footprint "eagle-import:C0805")
      (libsource (lib "eagle-import") (part "rcl_334_C-USC0805"))
    )
    (comp (ref "C38")
      (value "1uF")
      (footprint "eagle-import:C0805")
      (libsource (lib "eagle-import") (part "rcl_334_C-USC0805"))
    )
    (comp (ref "C39")
      (value "100nF")
      (footprint "eagle-import:C0805K")
      (libsource (lib "eagle-import") (part "rcl_334_C-USC0805K"))
    )
    (comp (ref "C40")
      (value "100nF")
      (footprint "eagle-import:C0805K")
      (libsource (lib "eagle-import") (part "rcl_334_C-USC0805K"))
    )
    (comp (ref "D6")
      (value "GF1J-E3DO-214BA-L")
      (footprint "eagle-import:DO-214BA-L")
      (fields (field (name "MANUFACTURER_PART_NUMBER") "GF1J-E3"))
      (libsource (lib "eagle-import") (part "GF1J-E3DO-214BA-L"))
    )
    (comp (ref "D7")
      (value "GF1J-E3DO-214BA-L")
      (footprint "eagle-import:DO-214BA-L")
      (fields (field (name "MANUFACTURER_PART_NUMBER") "GF1J-E3"))
      (libsource (lib "eagle-import") (part "GF1J-E3DO-214BA-L"))
    )
    (comp (ref "D8")
      (value "GF1J-E3DO-214BA-L")
      (footprint "eagle-import:DO-214BA-L")
      (fields (field (name "MANUFACTURER_PART_NUMBER") "GF1J-E3"))
      (libsource (lib "eagle-import") (part "GF1J-E3DO-214BA-L"))
    )
    (comp (ref "D9")
      (value "GF1J-E3DO-214BA-L")
      (footprint "eagle-import:DO-214BA-L")
      (fields (field (name "MANUFACTURER_PART_NUMBER") "GF1J-E3"))
      (libsource (lib "eagle-import") (part "GF1J-E3DO-214BA-L"))
    )
    (comp (ref "F2")
      (value "0453.062MR")
      (footprint "eagle-import:FUSC6127X294N")
      (libsource (lib "eagle-import") (part "0453.062MR"))
    )
    (comp (ref "F3")
      (value "0453.062MR")
      (footprint "eagle-import:FUSC6127X294N")
      (libsource (lib "eagle-import") (part "0453.062MR"))
    )
    (comp (ref "IC5")
      (value "INA149AID")
      (footprint "eagle-import:SOIC127P600X175-8N")
      (fields (field (name "MOUSER_PART_NUMBER") "595-INA149AID"))
      (libsource (lib "eagle-import") (part "INA149AID"))
    )
    (comp (ref "IC6")
      (value "TSC2012IST")
      (footprint "eagle-import:SOP65P490X110-8N")
      (fields
        (field (name "MANUFACTURER_PART_NUMBER") "TSC2011IST")
        (field (name "MOUSER_PART_NUMBER") "511-TSC2011IST")
      )
      (libsource (lib "eagle-import") (part "TSC2012IST"))
    )
    (comp (ref "IC7")
      (value "OPA140AID")
      (footprint "eagle-import:SOIC127P600X175-8N")
      (fields (field (name "MOUSER_PART_NUMBER") "595-OPA140AID"))
      (libsource (lib "eagle-import") (part "OPA140AID"))
    )
    (comp (ref "IC8")
      (value "INA149AID")
      (footprint "eagle-import:SOIC127P600X175-8N")
      (fields (field (name "MOUSER_PART_NUMBER") "595-INA149AID"))
      (libsource (lib "eagle-import") (part "INA149AID"))
    )
    (comp (ref "IC10")
      (value "OPA140AID")
      (footprint "eagle-import:SOIC127P600X175-8N")
      (fields (field (name "MOUSER_PART_NUMBER") "595-OPA140AID"))
      (libsource (lib "eagle-import") (part "OPA140AID"))
    )
    (comp (ref "J3")
      (value "DC_JACK_081BB-2103300")
      (footprint "eagle-import:081BB-2103300")
      (libsource (lib "eagle-import") (part "DC_JACK_081BB-2103300"))
    )
    (comp (ref "J4")
      (value "DC_JACK_081BB-2103300")
      (footprint "eagle-import:081BB-2103300")
      (libsource (lib "eagle-import") (part "DC_JACK_081BB-2103300"))
    )
    (comp (ref "K1")
      (value "CPC2125N")
      (footprint "eagle-import:SOP254P610X218-8N")
      (fields (field (name "MOUSER_PART_NUMBER") "849-CPC2125N"))
      (libsource (lib "eagle-import") (part "CPC2125N"))
    )
    (comp (ref "Q1")
      (value "MJE350")
      (footprint "eagle-import:TO229P300X760X1364-3P")
      (fields
        (field (name "MANUFACTURER_PART_NUMBER") "MJE350G")
        (field (name "MOUSER_PART_NUMBER") "863-MJE350G")
      )
      (libsource (lib "eagle-import") (part "MJE350"))
    )
    (comp (ref "Q2")
      (value "MJE340")
      (footprint "eagle-import:TO229P290X760X1320-3P")
      (fields (field (name "MOUSER_PART_NUMBER") "511-MJE340"))
      (libsource (lib "eagle-import") (part "MJE340"))
    )
    (comp (ref "Q3")
      (value "MJE350")
      (footprint "eagle-import:TO229P300X760X1364-3P")
      (fields
        (field (name "MANUFACTURER_PART_NUMBER") "MJE350G")
        (field (name "MOUSER_PART_NUMBER") "863-MJE350G")
      )
      (libsource (lib "eagle-import") (part "MJE350"))
    )
    (comp (ref "Q4")
      (value "MJE340")
      (footprint "eagle-import:TO229P290X760X1320-3P")
      (fields (field (name "MOUSER_PART_NUMBER") "511-MJE340"))
      (libsource (lib "eagle-import") (part "MJE340"))
    )
    (comp (ref "R10")
      (value "0.5E")
      (footprint "eagle-import:R1206")
      (libsource (lib "eagle-import") (part "rcl_334_R-US_R1206"))
    )
    (comp (ref "R11")
      (value "35.7K")
      (footprint "eagle-import:R1206")
      (libsource (lib "eagle-import") (part "rcl_334_R-US_R1206"))
    )
    (comp (ref "R12")
      (value "10K, 1/2W")
      (footprint "eagle-import:R1206")
      (libsource (lib "eagle-import") (part "rcl_334_R-US_R1206"))
    )
    (comp (ref "R13")
      (value "10K, 1/2W")
      (footprint "eagle-import:R1206")
      (libsource (lib "eagle-import") (part "rcl_334_R-US_R1206"))
    )
    (comp (ref "R14")
      (value "35.7K")
      (footprint "eagle-import:R1206")
      (libsource (lib "eagle-import") (part "rcl_334_R-US_R1206"))
    )
    (comp (ref "R15")
      (value "100E, 1/2W")
      (footprint "eagle-import:R1206")
      (libsource (lib "eagle-import") (part "rcl_334_R-US_R1206"))
    )
    (comp (ref "R16")
      (value "10E, 3/4W")
      (footprint "eagle-import:R1206")
      (libsource (lib "eagle-import") (part "rcl_334_R-US_R1206"))
    )
    (comp (ref "R18")
      (value "35.7K")
      (footprint "eagle-import:R1206")
      (libsource (lib "eagle-import") (part "rcl_334_R-US_R1206"))
    )
    (comp (ref "R19")
      (value "10K, 1/2W")
      (footprint "eagle-import:R1206")
      (libsource (lib "eagle-import") (part "rcl_334_R-US_R1206"))
    )
    (comp (ref "R20")
      (value "10K, 1/2W")
      (footprint "eagle-import:R1206")
      (libsource (lib "eagle-import") (part "rcl_334_R-US_R1206"))
    )
    (comp (ref "R21")
      (value "35.7K")
      (footprint "eagle-import:R1206")
      (libsource (lib "eagle-import") (part "rcl_334_R-US_R1206"))
    )
    (comp (ref "R22")
      (value "100E, 1/2W")
      (footprint "eagle-import:R1206")
      (libsource (lib "eagle-import") (part "rcl_334_R-US_R1206"))
    )
    (comp (ref "R23")
      (value "10E, 3/4W")
      (footprint "eagle-import:R1206")
      (libsource (lib "eagle-import") (part "rcl_334_R-US_R1206"))
    )
    (comp (ref "R24")
      (value "0E")
      (footprint "eagle-import:R1206")
      (libsource (lib "eagle-import") (part "rcl_334_R-US_R1206"))
    )
    (comp (ref "R25")
      (value "0E")
      (footprint "eagle-import:R1206")
      (libsource (lib "eagle-import") (part "rcl_334_R-US_R1206"))
    )
    (comp (ref "R28")
      (value "330E")
      (footprint "eagle-import:R0603")
      (libsource (lib "eagle-import") (part "R-US_R0603"))
    )
    (comp (ref "R36")
      (value "330E")
      (footprint "eagle-import:R1206")
      (libsource (lib "eagle-import") (part "R-US_R1206"))
    )
    (comp (ref "R37")
      (value "330E")
      (footprint "eagle-import:R1206")
      (libsource (lib "eagle-import") (part "R-US_R1206"))
    )
    (comp (ref "U9")
      (value "MAX6018BEUR16+T")
      (footprint "eagle-import:21-0051H_MXM")
      (libsource (lib "eagle-import") (part "MAX6018BEUR16+T"))
    )
    (comp (ref "V1")
      (value "TPTP10R")
      (footprint "eagle-import:TP10R")
      (libsource (lib "eagle-import") (part "TPTP10R"))
    )
    (comp (ref "V2")
      (value "TPTP10R")
      (footprint "eagle-import:TP10R")
      (libsource (lib "eagle-import") (part "TPTP10R"))
    )
    (comp (ref "V3")
      (value "TPTP10R")
      (footprint "eagle-import:TP10R")
      (libsource (lib "eagle-import") (part "TPTP10R"))
    )
    (comp (ref "V4")
      (value "TPTP10R")
      (footprint "eagle-import:TP10R")
      (libsource (lib "eagle-import") (part "TPTP10R"))
    )
    (comp (ref "VF/B1")
      (value "TPTP10R")
      (footprint "eagle-import:TP10R")
      (libsource (lib "eagle-import") (part "TPTP10R"))
    )
    (comp (ref "VF/B2")
      (value "TPTP10R")
      (footprint "eagle-import:TP10R")
      (libsource (lib "eagle-import") (part "TPTP10R"))
    )
  )
  (nets
    (net (code "1") (name "+3V3") (class "Default")
      (node (ref "3.3V") (pin "TP") (pinfunction "TP_TP") (pintype "input"))
      (node (ref "3V3") (pin "TP") (pinfunction "TP_TP") (pintype "input"))
      (node (ref "C19") (pin "1") (pinfunction "1_1") (pintype "passive"))
      (node (ref "C3") (pin "1") (pinfunction "1_1") (pintype "passive"))
      (node (ref "C4") (pin "1") (pinfunction "1_1") (pintype "passive"))
      (node (ref "C5") (pin "1") (pinfunction "1_1") (pintype "passive"))
      (node (ref "IC11") (pin "3") (pinfunction "VDD1_3") (pintype "bidirectional"))
      (node (ref "IC13") (pin "5") (pinfunction "OUT_5") (pintype "bidirectional"))
      (node (ref "IC15") (pin "10") (pinfunction "VDD_1_10") (pintype "bidirectional"))
      (node (ref "IC15") (pin "19") (pinfunction "AVDD_19") (pintype "bidirectional"))
      (node (ref "IC15") (pin "26") (pinfunction "VDD_2_26") (pintype "bidirectional"))
      (node (ref "IC15") (pin "38") (pinfunction "VDD_3_38") (pintype "bidirectional"))
      (node (ref "IC15") (pin "57") (pinfunction "VDD_4_57") (pintype "bidirectional"))
      (node (ref "J1") (pin "2") (pinfunction "S_2") (pintype "passive"))
      (node (ref "R1") (pin "2") (pinfunction "2_2") (pintype "passive"))
      (node (ref "R17") (pin "2") (pinfunction "2_2") (pintype "passive"))
      (node (ref "R3") (pin "1") (pinfunction "1_1") (pintype "passive"))
      (node (ref "R36") (pin "2") (pinfunction "2_2") (pintype "passive"))
      (node (ref "R37") (pin "2") (pinfunction "2_2") (pintype "passive"))
      (node (ref "R4") (pin "1") (pinfunction "1_1") (pintype "passive"))
      (node (ref "R8") (pin "1") (pinfunction "1_1") (pintype "passive"))
      (node (ref "RN1") (pin "2") (pinfunction "R1_2_2") (pintype "bidirectional"))
      (node (ref "RN2") (pin "6") (pinfunction "6_6") (pintype "bidirectional"))
      (node (ref "RN2") (pin "7") (pinfunction "7_7") (pintype "bidirectional"))
      (node (ref "S2") (pin "3") (pinfunction "A_3") (pintype "bidirectional"))
    )
    (net (code "2") (name "+5V") (class "Default")
      (node (ref "+5V") (pin "TP") (pinfunction "TP_TP") (pintype "input"))
      (node (ref "C12") (pin "1") (pinfunction "1_1") (pintype "passive"))
      (node (ref "C14") (pin "1") (pinfunction "1_1") (pintype "passive"))
      (node (ref "C21") (pin "1") (pinfunction "1_1") (pintype "passive"))
      (node (ref "C34") (pin "1") (pinfunction "+_1") (pintype "bidirectional"))
      (node (ref "C7") (pin "1") (pinfunction "1_1") (pintype "passive"))
      (node (ref "C8") (pin "1") (pinfunction "1_1") (pintype "passive"))
      (node (ref "C9") (pin "1") (pinfunction "1_1") (pintype "passive"))
      (node (ref "IC11") (pin "10") (pinfunction "VDD2_10") (pintype "bidirectional"))
      (node (ref "IC12") (pin "4") (pinfunction "VDD_4") (pintype "bidirectional"))
      (node (ref "IC3") (pin "8") (pinfunction "VCC_8") (pintype "power_in"))
      (node (ref "IC4") (pin "8") (pinfunction "VCC_8") (pintype "power_in"))
      (node (ref "IC6") (pin "6") (pinfunction "VCC_6") (pintype "bidirectional"))
      (node (ref "IC9") (pin "14") (pinfunction "~{WP}_14") (pintype "bidirectional"))
      (node (ref "IC9") (pin "15") (pinfunction "~{RESET}_15") (pintype "bidirectional"))
      (node (ref "IC9") (pin "17") (pinfunction "VDD_17") (pintype "power_in"))
      (node (ref "PS3") (pin "4") (pinfunction "+VOUT_4") (pintype "bidirectional"))
      (node (ref "R9") (pin "1") (pinfunction "1_1") (pintype "passive"))
      (node (ref "RN1") (pin "4") (pinfunction "R2_2_4") (pintype "bidirectional"))
      (node (ref "RN1") (pin "6") (pinfunction "R3_2_6") (pintype "bidirectional"))
      (node (ref "RN1") (pin "8") (pinfunction "R4_2_8") (pintype "bidirectional"))
      (node (ref "RN2") (pin "5") (pinfunction "5_5") (pintype "bidirectional"))
      (node (ref "U9") (pin "1") (pinfunction "IN_1") (pintype "input"))
    )
    (net (code "3") (name "AD3") (class "Default")
      (node (ref "JP7") (pin "4") (pinfunction "4_4") (pintype "passive"))
    )
    (net (code "4") (name "AD4") (class "Default")
      (node (ref "JP7") (pin "5") (pinfunction "5_5") (pintype "passive"))
    )
    (net (code "5") (name "AD5") (class "Default")
      (node (ref "JP7") (pin "6") (pinfunction "6_6") (pintype "passive"))
    )
    (net (code "6") (name "AD6") (class "Default")
      (node (ref "JP7") (pin "7") (pinfunction "7_7") (pintype "passive"))
    )
    (net (code "7") (name "AD7") (class "Default")
      (node (ref "JP7") (pin "8") (pinfunction "8_8") (pintype "passive"))
    )
    (net (code "8") (name "AD8") (class "Default")
      (node (ref "JP8") (pin "1") (pinfunction "1_1") (pintype "passive"))
    )
    (net (code "9") (name "AD9") (class "Default")
      (node (ref "JP8") (pin "2") (pinfunction "2_2") (pintype "passive"))
    )
    (net (code "10") (name "AD10") (class "Default")
      (node (ref "JP8") (pin "3") (pinfunction "3_3") (pintype "passive"))
    )
    (net (code "11") (name "AD11(TXD3)") (class "Default")
      (node (ref "JP8") (pin "4") (pinfunction "4_4") (pintype "passive"))
    )
    (net (code "12") (name "AGND") (class "Default")
      (node (ref "AGND") (pin "TP") (pinfunction "TP_TP") (pintype "input"))
      (node (ref "C11") (pin "2") (pinfunction "2_2") (pintype "passive"))
      (node (ref "C12") (pin "2") (pinfunction "2_2") (pintype "passive"))
      (node (ref "C14") (pin "2") (pinfunction "2_2") (pintype "passive"))
      (node (ref "C21") (pin "2") (pinfunction "2_2") (pintype "passive"))
      (node (ref "C31") (pin "1") (pinfunction "1_1") (pintype "passive"))
      (node (ref "C32") (pin "2") (pinfunction "2_2") (pintype "passive"))
      (node (ref "C34") (pin "2") (pinfunction "-_2") (pintype "bidirectional"))
      (node (ref "C35") (pin "2") (pinfunction "2_2") (pintype "passive"))
      (node (ref "C36") (pin "2") (pinfunction "2_2") (pintype "passive"))
      (node (ref "C37") (pin "2") (pinfunction "2_2") (pintype "passive"))
      (node (ref "C38") (pin "2") (pinfunction "2_2") (pintype "passive"))
      (node (ref "C7") (pin "2") (pinfunction "2_2") (pintype "passive"))
      (node (ref "C8") (pin "2") (pinfunction "2_2") (pintype "passive"))
      (node (ref "C9") (pin "2") (pinfunction "2_2") (pintype "passive"))
      (node (ref "IC11") (pin "14") (pinfunction "GND2_2_14") (pintype "bidirectional"))
      (node (ref "IC11") (pin "9") (pinfunction "GND2_1_9") (pintype "bidirectional"))
      (node (ref "IC12") (pin "11") (pinfunction "VSS_11") (pintype "bidirectional"))
      (node (ref "IC3") (pin "5") (pinfunction "GND_5") (pintype "power_in"))
      (node (ref "IC4") (pin "5") (pinfunction "GND_5") (pintype "power_in"))
      (node (ref "IC6") (pin "1") (pinfunction "IN-_1") (pintype "bidirectional"))
      (node (ref "IC6") (pin "2") (pinfunction "GND_2") (pintype "bidirectional"))
      (node (ref "IC6") (pin "4") (pinfunction "SHDN_4") (pintype "bidirectional"))
      (node (ref "IC9") (pin "13") (pinfunction "P0B_13") (pintype "bidirectional"))
      (node (ref "IC9") (pin "18") (pinfunction "P2B_18") (pintype "bidirectional"))
      (node (ref "IC9") (pin "3") (pinfunction "P3B_3") (pintype "bidirectional"))
      (node (ref "IC9") (pin "7") (pinfunction "VSS_7") (pintype "power_in"))
      (node (ref "IC9") (pin "8") (pinfunction "P1B_8") (pintype "bidirectional"))
      (node (ref "PS1") (pin "5") (pinfunction "+VOUT_5") (pintype "bidirectional"))
      (node (ref "PS2") (pin "8") (pinfunction "-VOUT3_8") (pintype "bidirectional"))
      (node (ref "PS3") (pin "3") (pinfunction "-VOUT_3") (pintype "bidirectional"))
      (node (ref "R10") (pin "1") (pinfunction "1_1") (pintype "passive"))
      (node (ref "R25") (pin "2") (pinfunction "2_2") (pintype "passive"))
      (node (ref "U9") (pin "3") (pinfunction "GND_3") (pintype "power_in"))
    )
    (net (code "13") (name "AREF") (class "Default")
      (node (ref "JP3") (pin "8") (pinfunction "8_8") (pintype "passive"))
    )
    (net (code "14") (name "BD+") (class "Default")
      (node (ref "IC2") (pin "15") (pinfunction "USBDP_15") (pintype "bidirectional"))
      (node (ref "J2") (pin "3") (pinfunction "D+_3") (pintype "bidirectional"))
      (node (ref "TP1") (pin "X") (pinfunction "P$1_X") (pintype "passive"))
    )
    (net (code "15") (name "BD-") (class "Default")
      (node (ref "IC2") (pin "16") (pinfunction "USBDM_16") (pintype "bidirectional"))
      (node (ref "J2") (pin "2") (pinfunction "D-_2") (pintype "bidirectional"))
      (node (ref "TP2") (pin "X") (pinfunction "P$1_X") (pintype "passive"))
    )
    (net (code "16") (name "CANRX0") (class "Default")
      (node (ref "JP8") (pin "7") (pinfunction "7_7") (pintype "passive"))
    )
    (net (code "17") (name "CANTX0") (class "Default")
      (node (ref "JP8") (pin "8") (pinfunction "8_8") (pintype "passive"))
    )
    (net (code "18") (name "CH1_EN~{}") (class "Default")
      (node (ref "IC15") (pin "15") (pinfunction "PGEC3/AN1/CMP1B/CN3/RB1_15") (pintype "bidirectional"))
      (node (ref "K1") (pin "2") (pinfunction "-_CONTROL_1_2") (pintype "bidirectional"))
    )
    (net (code "19") (name "CH2_EN~{}") (class "Default")
      (node (ref "IC15") (pin "14") (pinfunction "AN2/CMP1C/CMP2A/~{ASS1}/CN4/RB2_14") (pintype "bidirectional"))
      (node (ref "K1") (pin "4") (pinfunction "-_CONTROL_2_4") (pintype "bidirectional"))
    )
    (net (code "20") (name "COMM_RET") (class "Default")
      (node (ref "IC6") (pin "8") (pinfunction "IN+_8") (pintype "bidirectional"))
      (node (ref "J3") (pin "P$2") (pinfunction "2_P$2") (pintype "passive"))
      (node (ref "J3") (pin "P$3") (pinfunction "3_P$3") (pintype "passive"))
      (node (ref "J4") (pin "P$2") (pinfunction "2_P$2") (pintype "passive"))
      (node (ref "J4") (pin "P$3") (pinfunction "3_P$3") (pintype "passive"))
      (node (ref "R10") (pin "2") (pinfunction "2_2") (pintype "passive"))
      (node (ref "R16") (pin "2") (pinfunction "2_2") (pintype "passive"))
      (node (ref "R23") (pin "2") (pinfunction "2_2") (pintype "passive"))
    )
    (net (code "21") (name "CS_DIGIPOT") (class "Default")
      (node (ref "CS1") (pin "TP") (pinfunction "TP_TP") (pintype "input"))
      (node (ref "IC15") (pin "8") (pinfunction "~{SS2}/FLT9/SYNCI2/T5CK/CN11/RG9_8") (pintype "bidirectional"))
      (node (ref "RN2") (pin "8") (pinfunction "8_8") (pintype "bidirectional"))
    )
    (net (code "22") (name "CS_ISO") (class "Default")
      (node (ref "IC11") (pin "13") (pinfunction "V01_13") (pintype "bidirectional"))
      (node (ref "IC9") (pin "4") (pinfunction "~{CS}_4") (pintype "input"))
      (node (ref "RN1") (pin "3") (pinfunction "R2_1_3") (pintype "bidirectional"))
    )
    (net (code "23") (name "D9") (class "Default")
      (node (ref "IC15") (pin "43") (pinfunction "IC2/FLT2/~{U1CTS}/INT2/RD9_43") (pintype "bidirectional"))
      (node (ref "JP3") (pin "2") (pinfunction "2_2") (pintype "passive"))
      (node (ref "R26") (pin "2") (pinfunction "2_2") (pintype "passive"))
    )
    (net (code "24") (name "D10") (class "Default")
      (node (ref "IC15") (pin "42") (pinfunction "IC1/FLT1/SYNCI1/INT1/RD8_42") (pintype "bidirectional"))
      (node (ref "JP3") (pin "3") (pinfunction "3_3") (pintype "passive"))
      (node (ref "R27") (pin "2") (pinfunction "2_2") (pintype "passive"))
    )
    (net (code "25") (name "DAC0(CANRX1)") (class "Default")
      (node (ref "JP8") (pin "5") (pinfunction "5_5") (pintype "passive"))
    )
    (net (code "26") (name "DAC1") (class "Default")
      (node (ref "JP8") (pin "6") (pinfunction "6_6") (pintype "passive"))
    )
    (net (code "27") (name "DC_5V") (class "Default")
      (node (ref "C27") (pin "1") (pinfunction "1_1") (pintype "passive"))
      (node (ref "IC14") (pin "4") (pinfunction "OUT_4") (pintype "bidirectional"))
      (node (ref "R32") (pin "1") (pinfunction "1_1") (pintype "passive"))
      (node (ref "U6") (pin "1") (pinfunction "VIN_1") (pintype "power_in"))
      (node (ref "U7") (pin "3") (pinfunction "D_3") (pintype "passive"))
    )
    (net (code "28") (name "EOFF_R~{}") (class "Default")
      (node (ref "IC15") (pin "18") (pinfunction "PGED1/AN7/CMP4B/RB7_18") (pintype "bidirectional"))
      (node (ref "Q8") (pin "1") (pinfunction "B_1") (pintype "bidirectional"))
    )
    (net (code "29") (name "ERR_FLG") (class "Default")
      (node (ref "IC14") (pin "3") (pinfunction "FLG_3") (pintype "bidirectional"))
      (node (ref "IC15") (pin "44") (pinfunction "IC3/INDX1/FLT3/INT3/RD10_44") (pintype "bidirectional"))
      (node (ref "R32") (pin "2") (pinfunction "2_2") (pintype "passive"))
    )
    (net (code "30") (name "GND") (class "Default")
      (node (ref "C1") (pin "2") (pinfunction "2_2") (pintype "passive"))
      (node (ref "C19") (pin "2") (pinfunction "2_2") (pintype "passive"))
      (node (ref "C2") (pin "2") (pinfunction "-_2") (pintype "bidirectional"))
      (node (ref "C25") (pin "2") (pinfunction "2_2") (pintype "passive"))
      (node (ref "C26") (pin "2") (pinfunction "2_2") (pintype "passive"))
      (node (ref "C27") (pin "2") (pinfunction "2_2") (pintype "passive"))
      (node (ref "C28") (pin "2") (pinfunction "2_2") (pintype "passive"))
      (node (ref "C29") (pin "-") (pinfunction "-_-") (pintype "passive"))
      (node (ref "C3") (pin "2") (pinfunction "2_2") (pintype "passive"))
      (node (ref "C30") (pin "2") (pinfunction "-_2") (pintype "bidirectional"))
      (node (ref "C4") (pin "2") (pinfunction "2_2") (pintype "passive"))
      (node (ref "C5") (pin "2") (pinfunction "2_2") (pintype "passive"))
      (node (ref "C6") (pin "2") (pinfunction "2_2") (pintype "passive"))
      (node (ref "DGND") (pin "TP") (pinfunction "TP_TP") (pintype "input"))
      (node (ref "GND") (pin "TP") (pinfunction "TP_TP") (pintype "input"))
      (node (ref "IC11") (pin "1") (pinfunction "GND1_CATHODE1_1") (pintype "bidirectional"))
      (node (ref "IC13") (pin "2") (pinfunction "GND_2") (pintype "bidirectional"))
      (node (ref "IC14") (pin "5") (pinfunction "GND_1_5") (pintype "bidirectional"))
      (node (ref "IC14") (pin "6") (pinfunction "GND_2_6") (pintype "bidirectional"))
      (node (ref "IC14") (pin "7") (pinfunction "GND_3_7") (pintype "bidirectional"))
      (node (ref "IC14") (pin "8") (pinfunction "GND_4_8") (pintype "bidirectional"))
      (node (ref "IC15") (pin "20") (pinfunction "AVSS_20") (pintype "bidirectional"))
      (node (ref "IC15") (pin "25") (pinfunction "VSS_2_25") (pintype "bidirectional"))
      (node (ref "IC15") (pin "41") (pinfunction "VSS_3_41") (pintype "bidirectional"))
      (node (ref "IC15") (pin "9") (pinfunction "VSS_1_9") (pintype "bidirectional"))
      (node (ref "IC2") (pin "18") (pinfunction "GND_18") (pintype "power_in"))
      (node (ref "IC2") (pin "21") (pinfunction "GND_21") (pintype "power_in"))
      (node (ref "IC2") (pin "25") (pinfunction "GND_25") (pintype "power_in"))
      (node (ref "IC2") (pin "26") (pinfunction "TEST_26") (pintype "input"))
      (node (ref "IC2") (pin "7") (pinfunction "GND_7") (pintype "power_in"))
      (node (ref "J1") (pin "3") (pinfunction "S_3") (pintype "passive"))
      (node (ref "J2") (pin "5") (pinfunction "GND_5") (pintype "bidirectional"))
      (node (ref "J7") (pin "2") (pinfunction "2_2") (pintype "bidirectional"))
      (node (ref "J7") (pin "3") (pinfunction "3_3") (pintype "bidirectional"))
      (node (ref "JP3") (pin "7") (pinfunction "7_7") (pintype "passive"))
      (node (ref "JP6") (pin "6") (pinfunction "6_6") (pintype "passive"))
      (node (ref "JP6") (pin "7") (pinfunction "7_7") (pintype "passive"))
      (node (ref "LED5") (pin "C") (pinfunction "C_C") (pintype "passive"))
      (node (ref "LED6") (pin "C") (pinfunction "C_C") (pintype "passive"))
      (node (ref "LED7") (pin "C") (pinfunction "C_C") (pintype "passive"))
      (node (ref "LED8") (pin "C") (pinfunction "C_C") (pintype "passive"))
      (node (ref "PS1") (pin "2") (pinfunction "-VIN_2") (pintype "bidirectional"))
      (node (ref "PS2") (pin "2") (pinfunction "-VIN_2") (pintype "bidirectional"))
      (node (ref "PS3") (pin "1") (pinfunction "-VIN_(GND)_1") (pintype "bidirectional"))
      (node (ref "Q8") (pin "3") (pinfunction "C_3") (pintype "bidirectional"))
      (node (ref "R25") (pin "1") (pinfunction "1_1") (pintype "passive"))
      (node (ref "S1") (pin "1") (pinfunction "1_1") (pintype "passive"))
      (node (ref "S2") (pin "1") (pinfunction "COM_1") (pintype "bidirectional"))
      (node (ref "TP4") (pin "X") (pinfunction "P$1_X") (pintype "passive"))
      (node (ref "U6") (pin "2") (pinfunction "GND_2") (pintype "passive"))
      (node (ref "U6") (pin "3") (pinfunction "CTL_3") (pintype "input"))
    )
    (net (code "31") (name "INT0") (class "Default")
      (node (ref "IC15") (pin "35") (pinfunction "~{U1RTS}/SCK1/INT0/RF6_35") (pintype "bidirectional"))
      (node (ref "R17") (pin "1") (pinfunction "1_1") (pintype "passive"))
      (node (ref "S2") (pin "2") (pinfunction "NO_2") (pintype "bidirectional"))
    )
    (net (code "32") (name "IOUT") (class "Default")
      (node (ref "IC15") (pin "22") (pinfunction "AN9/DACOUT/RB9_22") (pintype "bidirectional"))
      (node (ref "JP7") (pin "1") (pinfunction "1_1") (pintype "passive"))
      (node (ref "R24") (pin "1") (pinfunction "1_1") (pintype "passive"))
    )
    (net (code "33") (name "MASTER-RESET") (class "Default")
      (node (ref "C1") (pin "1") (pinfunction "1_1") (pintype "passive"))
      (node (ref "JP6") (pin "3") (pinfunction "3_3") (pintype "passive"))
      (node (ref "R1") (pin "1") (pinfunction "1_1") (pintype "passive"))
      (node (ref "R2") (pin "1") (pinfunction "1_1") (pintype "passive"))
      (node (ref "S1") (pin "3") (pinfunction "2_3") (pintype "passive"))
    )
    (net (code "34") (name "Net-(C2-+)") (class "Default")
      (node (ref "C2") (pin "1") (pinfunction "+_1") (pintype "bidirectional"))
      (node (ref "IC15") (pin "56") (pinfunction "VCAP_56") (pintype "bidirectional"))
    )
    (net (code "35") (name "Net-(C11-Pad1)") (class "Default")
      (node (ref "C11") (pin "1") (pinfunction "1_1") (pintype "passive"))
      (node (ref "R24") (pin "2") (pinfunction "2_2") (pintype "passive"))
      (node (ref "R28") (pin "2") (pinfunction "2_2") (pintype "passive"))
    )
    (net (code "36") (name "Net-(D2-A)") (class "Default")
      (node (ref "D2") (pin "P$2") (pinfunction "A_P$2") (pintype "bidirectional"))
      (node (ref "D3") (pin "A") (pinfunction "A_A") (pintype "passive"))
      (node (ref "L1") (pin "1") (pinfunction "1_1") (pintype "passive"))
    )
    (net (code "37") (name "Net-(D5-A)") (class "Default")
      (node (ref "D5") (pin "2") (pinfunction "A_2") (pintype "bidirectional"))
      (node (ref "JP6") (pin "5") (pinfunction "5_5") (pintype "passive"))
    )
    (net (code "38") (name "Net-(D6-Pad2)") (class "Default")
      (node (ref "D6") (pin "2") (pinfunction "2_2") (pintype "passive"))
      (node (ref "R13") (pin "1") (pinfunction "1_1") (pintype "passive"))
    )
    (net (code "39") (name "Net-(D7-Pad1)") (class "Default")
      (node (ref "D7") (pin "1") (pinfunction "1_1") (pintype "passive"))
      (node (ref "R12") (pin "2") (pinfunction "2_2") (pintype "passive"))
    )
    (net (code "40") (name "Net-(D8-Pad2)") (class "Default")
      (node (ref "D8") (pin "2") (pinfunction "2_2") (pintype "passive"))
      (node (ref "R20") (pin "1") (pinfunction "1_1") (pintype "passive"))
    )
    (net (code "41") (name "Net-(D9-Pad1)") (class "Default")
      (node (ref "D9") (pin "1") (pinfunction "1_1") (pintype "passive"))
      (node (ref "R19") (pin "2") (pinfunction "2_2") (pintype "passive"))
    )
    (net (code "42") (name "Net-(IC2-3V3OUT)") (class "Default")
      (node (ref "IC2") (pin "17") (pinfunction "3V3OUT_17") (pintype "output"))
      (node (ref "IC2") (pin "4") (pinfunction "VCCIO_4") (pintype "power_in"))
    )
    (net (code "43") (name "Net-(IC2-CBUS0)") (class "Default")
      (node (ref "IC2") (pin "23") (pinfunction "CBUS0_23") (pintype "bidirectional"))
      (node (ref "LED2") (pin "C") (pinfunction "C_C") (pintype "passive"))
    )
    (net (code "44") (name "Net-(IC2-CBUS1)") (class "Default")
      (node (ref "IC2") (pin "22") (pinfunction "CBUS1_22") (pintype "bidirectional"))
      (node (ref "LED1") (pin "C") (pinfunction "C_C") (pintype "passive"))
    )
    (net (code "45") (name "Net-(IC2-CBUS3)") (class "Default")
      (node (ref "IC2") (pin "14") (pinfunction "CBUS3_14") (pintype "bidirectional"))
      (node (ref "R6") (pin "1") (pinfunction "1_1") (pintype "passive"))
    )
    (net (code "46") (name "Net-(IC3-V01)") (class "Default")
      (node (ref "IC3") (pin "7") (pinfunction "V01_7") (pintype "bidirectional"))
      (node (ref "IC9") (pin "20") (pinfunction "P2A_20") (pintype "bidirectional"))
      (node (ref "R9") (pin "2") (pinfunction "2_2") (pintype "passive"))
    )
    (net (code "47") (name "Net-(IC3-V02)") (class "Default")
      (node (ref "IC3") (pin "6") (pinfunction "V02_6") (pintype "bidirectional"))
      (node (ref "IC9") (pin "1") (pinfunction "P3A_1") (pintype "bidirectional"))
      (node (ref "R9") (pin "3") (pinfunction "3_3") (pintype "passive"))
    )
    (net (code "48") (name "Net-(IC3-VF1+)") (class "Default")
      (node (ref "IC3") (pin "1") (pinfunction "VF1+_1") (pintype "bidirectional"))
      (node (ref "R8") (pin "3") (pinfunction "3_3") (pintype "passive"))
    )
    (net (code "49") (name "Net-(IC3-VF2+)") (class "Default")
      (node (ref "IC3") (pin "4") (pinfunction "VF2+_4") (pintype "bidirectional"))
      (node (ref "R8") (pin "2") (pinfunction "2_2") (pintype "passive"))
    )
    (net (code "50") (name "Net-(IC4-V01)") (class "Default")
      (node (ref "IC4") (pin "7") (pinfunction "V01_7") (pintype "bidirectional"))
      (node (ref "IC9") (pin "11") (pinfunction "P0A_11") (pintype "bidirectional"))
      (node (ref "R9") (pin "4") (pinfunction "4_4") (pintype "passive"))
    )
    (net (code "51") (name "Net-(IC4-V02)") (class "Default")
      (node (ref "IC4") (pin "6") (pinfunction "V02_6") (pintype "bidirectional"))
      (node (ref "IC9") (pin "10") (pinfunction "P1A_10") (pintype "bidirectional"))
      (node (ref "R9") (pin "5") (pinfunction "5_5") (pintype "passive"))
    )
    (net (code "52") (name "Net-(IC4-VF1+)") (class "Default")
      (node (ref "IC4") (pin "1") (pinfunction "VF1+_1") (pintype "bidirectional"))
      (node (ref "R8") (pin "5") (pinfunction "5_5") (pintype "passive"))
    )
    (net (code "53") (name "Net-(IC4-VF2+)") (class "Default")
      (node (ref "IC4") (pin "4") (pinfunction "VF2+_4") (pintype "bidirectional"))
      (node (ref "R8") (pin "4") (pinfunction "4_4") (pintype "passive"))
    )
    (net (code "54") (name "Net-(IC5-REF_A)") (class "Default")
      (node (ref "IC5") (pin "1") (pinfunction "REF_B_1") (pintype "input"))
      (node (ref "IC5") (pin "5") (pinfunction "REF_A_5") (pintype "input"))
      (node (ref "IC7") (pin "2") (pinfunction "-IN_2") (pintype "input"))
      (node (ref "IC7") (pin "6") (pinfunction "OUT_6") (pintype "output"))
      (node (ref "VF/B1") (pin "TP") (pinfunction "TP_TP") (pintype "input"))
    )
    (net (code "55") (name "Net-(IC5-V+)") (class "Default")
      (node (ref "IC5") (pin "7") (pinfunction "V+_7") (pintype "power_in"))
      (node (ref "IC7") (pin "7") (pinfunction "V+_7") (pintype "bidirectional"))
      (node (ref "Q2") (pin "1") (pinfunction "E_1") (pintype "bidirectional"))
      (node (ref "V1") (pin "TP") (pinfunction "TP_TP") (pintype "input"))
    )
    (net (code "56") (name "Net-(IC5-V-)") (class "Default")
      (node (ref "IC5") (pin "4") (pinfunction "V-_4") (pintype "power_in"))
      (node (ref "IC7") (pin "4") (pinfunction "V-_4") (pintype "bidirectional"))
      (node (ref "Q1") (pin "1") (pinfunction "E_1") (pintype "bidirectional"))
      (node (ref "V2") (pin "TP") (pinfunction "TP_TP") (pintype "input"))
    )
    (net (code "57") (name "Net-(IC5-V_OUT)") (class "Default")
      (node (ref "D6") (pin "1") (pinfunction "1_1") (pintype "passive"))
      (node (ref "D7") (pin "2") (pinfunction "2_2") (pintype "passive"))
      (node (ref "IC5") (pin "6") (pinfunction "V_OUT_6") (pintype "output"))
      (node (ref "R15") (pin "2") (pinfunction "2_2") (pintype "passive"))
    )
    (net (code "58") (name "Net-(IC6-OUT)") (class "Default")
      (node (ref "IC6") (pin "5") (pinfunction "OUT_5") (pintype "bidirectional"))
      (node (ref "R28") (pin "1") (pinfunction "1_1") (pintype "passive"))
    )
    (net (code "59") (name "Net-(IC6-VREF1)") (class "Default")
      (node (ref "1.6V") (pin "TP") (pinfunction "TP_TP") (pintype "input"))
      (node (ref "IC6") (pin "3") (pinfunction "VREF2_3") (pintype "bidirectional"))
      (node (ref "IC6") (pin "7") (pinfunction "VREF1_7") (pintype "bidirectional"))
      (node (ref "U9") (pin "2") (pinfunction "OUT_2") (pintype "output"))
    )
    (net (code "60") (name "Net-(IC7-+IN)") (class "Default")
      (node (ref "F2") (pin "1") (pinfunction "1_1") (pintype "bidirectional"))
      (node (ref "IC7") (pin "3") (pinfunction "+IN_3") (pintype "input"))
      (node (ref "K1") (pin "8") (pinfunction "LOAD_4_8") (pintype "bidirectional"))
      (node (ref "R15") (pin "1") (pinfunction "1_1") (pintype "passive"))
    )
    (net (code "61") (name "Net-(IC8-V_OUT)") (class "Default")
      (node (ref "D8") (pin "1") (pinfunction "1_1") (pintype "passive"))
      (node (ref "D9") (pin "2") (pinfunction "2_2") (pintype "passive"))
      (node (ref "IC8") (pin "6") (pinfunction "V_OUT_6") (pintype "output"))
      (node (ref "R22") (pin "2") (pinfunction "2_2") (pintype "passive"))
    )
    (net (code "62") (name "Net-(IC10-+IN)") (class "Default")
      (node (ref "F3") (pin "1") (pinfunction "1_1") (pintype "bidirectional"))
      (node (ref "IC10") (pin "3") (pinfunction "+IN_3") (pintype "input"))
      (node (ref "K1") (pin "6") (pinfunction "LOAD_2_6") (pintype "bidirectional"))
      (node (ref "R22") (pin "1") (pinfunction "1_1") (pintype "passive"))
    )
    (net (code "63") (name "Net-(IC10--IN)") (class "Default")
      (node (ref "IC10") (pin "2") (pinfunction "-IN_2") (pintype "input"))
      (node (ref "IC10") (pin "6") (pinfunction "OUT_6") (pintype "output"))
      (node (ref "IC8") (pin "1") (pinfunction "REF_B_1") (pintype "input"))
      (node (ref "IC8") (pin "5") (pinfunction "REF_A_5") (pintype "input"))
      (node (ref "VF/B2") (pin "TP") (pinfunction "TP_TP") (pintype "input"))
    )
    (net (code "64") (name "Net-(IC10-V+)") (class "Default")
      (node (ref "IC10") (pin "7") (pinfunction "V+_7") (pintype "bidirectional"))
      (node (ref "IC8") (pin "7") (pinfunction "V+_7") (pintype "power_in"))
      (node (ref "Q4") (pin "1") (pinfunction "E_1") (pintype "bidirectional"))
      (node (ref "V3") (pin "TP") (pinfunction "TP_TP") (pintype "input"))
    )
    (net (code "65") (name "Net-(IC10-V-)") (class "Default")
      (node (ref "IC10") (pin "4") (pinfunction "V-_4") (pintype "bidirectional"))
      (node (ref "IC8") (pin "4") (pinfunction "V-_4") (pintype "power_in"))
      (node (ref "Q3") (pin "1") (pinfunction "E_1") (pintype "bidirectional"))
      (node (ref "V4") (pin "TP") (pinfunction "TP_TP") (pintype "input"))
    )
    (net (code "66") (name "Net-(IC11-ANODE1)") (class "Default")
      (node (ref "IC11") (pin "4") (pinfunction "ANODE1_4") (pintype "bidirectional"))
      (node (ref "RN2") (pin "1") (pinfunction "1_1") (pintype "bidirectional"))
    )
    (net (code "67") (name "Net-(IC11-ANODE2)") (class "Default")
      (node (ref "IC11") (pin "6") (pinfunction "ANODE2_6") (pintype "bidirectional"))
      (node (ref "RN2") (pin "2") (pinfunction "2_2") (pintype "bidirectional"))
    )
    (net (code "68") (name "Net-(IC11-ANODE3)") (class "Default")
      (node (ref "IC11") (pin "8") (pinfunction "ANODE3_8") (pintype "bidirectional"))
      (node (ref "RN2") (pin "3") (pinfunction "3_3") (pintype "bidirectional"))
    )
    (net (code "69") (name "Net-(IC11-ANODE4)") (class "Default")
      (node (ref "IC11") (pin "15") (pinfunction "ANODE4_15") (pintype "bidirectional"))
      (node (ref "RN2") (pin "4") (pinfunction "4_4") (pintype "bidirectional"))
    )
    (net (code "70") (name "Net-(IC13-NR{slash}FB)") (class "Default")
      (node (ref "C28") (pin "1") (pinfunction "1_1") (pintype "passive"))
      (node (ref "IC13") (pin "4") (pinfunction "NR/FB_4") (pintype "bidirectional"))
    )
    (net (code "71") (name "Net-(IC15-AN14{slash}CMP3D{slash}~{SS1}{slash}~{U2RTS}{slash}RB14)") (class "Default")
      (node (ref "IC15") (pin "29") (pinfunction "AN14/CMP3D/~{SS1}/~{U2RTS}/RB14_29") (pintype "bidirectional"))
      (node (ref "RB14") (pin "TP") (pinfunction "TP_TP") (pintype "input"))
    )
    (net (code "72") (name "Net-(IC15-AN15{slash}CMP4D{slash}CN12{slash}RB15)") (class "Default")
      (node (ref "IC15") (pin "30") (pinfunction "AN15/CMP4D/CN12/RB15_30") (pintype "bidirectional"))
      (node (ref "RB15") (pin "TP") (pinfunction "TP_TP") (pintype "input"))
    )
    (net (code "73") (name "Net-(IC15-C1RX{slash}SYNCI4{slash}RF0)") (class "Default")
      (node (ref "IC15") (pin "58") (pinfunction "C1RX/SYNCI4/RF0_58") (pintype "bidirectional"))
      (node (ref "RF0") (pin "TP") (pinfunction "TP_TP") (pintype "input"))
    )
    (net (code "74") (name "Net-(IC15-PWM1L{slash}FLT8{slash}RE0)") (class "Default")
      (node (ref "IC15") (pin "60") (pinfunction "PWM1L/FLT8/RE0_60") (pintype "bidirectional"))
      (node (ref "RG1") (pin "TP") (pinfunction "TP_TP") (pintype "input"))
    )
    (net (code "75") (name "Net-(IC15-PWM2L{slash}RE2)") (class "Default")
      (node (ref "IC15") (pin "62") (pinfunction "PWM2L/RE2_62") (pintype "bidirectional"))
      (node (ref "RG14") (pin "TP") (pinfunction "TP_TP") (pintype "input"))
    )
    (net (code "76") (name "Net-(IC15-PWM3L{slash}RE4)") (class "Default")
      (node (ref "IC15") (pin "64") (pinfunction "PWM3L/RE4_64") (pintype "bidirectional"))
      (node (ref "RG13") (pin "TP") (pinfunction "TP_TP") (pintype "input"))
    )
    (net (code "77") (name "Net-(IC15-PWM6H{slash}CN14{slash}RD5)") (class "Default")
      (node (ref "IC15") (pin "53") (pinfunction "PWM6H/CN14/RD5_53") (pintype "bidirectional"))
      (node (ref "OC6") (pin "TP") (pinfunction "TP_TP") (pintype "input"))
    )
    (net (code "78") (name "Net-(IC15-PWM6L{slash}CN13{slash}RD4)") (class "Default")
      (node (ref "IC15") (pin "52") (pinfunction "PWM6L/CN13/RD4_52") (pintype "bidirectional"))
      (node (ref "OC5") (pin "TP") (pinfunction "TP_TP") (pintype "input"))
    )
    (net (code "79") (name "Net-(IC15-TCK{slash}AN12{slash}CMP1D{slash}RB12)") (class "Default")
      (node (ref "IC15") (pin "27") (pinfunction "TCK/AN12/CMP1D/RB12_27") (pintype "bidirectional"))
      (node (ref "RB12") (pin "TP") (pinfunction "TP_TP") (pintype "input"))
    )
    (net (code "80") (name "Net-(IC15-TDI{slash}AN13{slash}CMP2D{slash}RB13)") (class "Default")
      (node (ref "IC15") (pin "28") (pinfunction "TDI/AN13/CMP2D/RB13_28") (pintype "bidirectional"))
      (node (ref "RB13") (pin "TP") (pinfunction "TP_TP") (pintype "input"))
    )
    (net (code "81") (name "Net-(IC15-U2RX{slash}SDA2{slash}QEA2{slash}FLT17{slash}CN17{slash}RF4)") (class "Default")
      (node (ref "IC15") (pin "31") (pinfunction "U2RX/SDA2/QEA2/FLT17/CN17/RF4_31") (pintype "bidirectional"))
      (node (ref "RX2/SDA2") (pin "TP") (pinfunction "TP_TP") (pintype "input"))
    )
    (net (code "82") (name "Net-(IC15-U2TX{slash}SCL2{slash}QEB2{slash}FLT18{slash}CN18{slash}RF5)") (class "Default")
      (node (ref "IC15") (pin "32") (pinfunction "U2TX/SCL2/QEB2/FLT18/CN18/RF5_32") (pintype "bidirectional"))
      (node (ref "TX2/SCL2") (pin "TP") (pinfunction "TP_TP") (pintype "input"))
    )
    (net (code "83") (name "Net-(J3-1)") (class "Default")
      (node (ref "F2") (pin "2") (pinfunction "2_2") (pintype "bidirectional"))
      (node (ref "J3") (pin "P$1") (pinfunction "1_P$1") (pintype "passive"))
    )
    (net (code "84") (name "Net-(J4-1)") (class "Default")
      (node (ref "F3") (pin "2") (pinfunction "2_2") (pintype "bidirectional"))
      (node (ref "J4") (pin "P$1") (pinfunction "1_P$1") (pintype "passive"))
    )
    (net (code "85") (name "Net-(K1-+_CONTROL_1)") (class "Default")
      (node (ref "K1") (pin "1") (pinfunction "+_CONTROL_1_1") (pintype "bidirectional"))
      (node (ref "R37") (pin "1") (pinfunction "1_1") (pintype "passive"))
    )
    (net (code "86") (name "Net-(K1-+_CONTROL_2)") (class "Default")
      (node (ref "K1") (pin "3") (pinfunction "+_CONTROL_2_3") (pintype "bidirectional"))
      (node (ref "R36") (pin "1") (pinfunction "1_1") (pintype "passive"))
    )
    (net (code "87") (name "Net-(K1-LOAD_1)") (class "Default")
      (node (ref "K1") (pin "5") (pinfunction "LOAD_1_5") (pintype "bidirectional"))
      (node (ref "R23") (pin "1") (pinfunction "1_1") (pintype "passive"))
    )
    (net (code "88") (name "Net-(K1-LOAD_3)") (class "Default")
      (node (ref "K1") (pin "7") (pinfunction "LOAD_3_7") (pintype "bidirectional"))
      (node (ref "R16") (pin "1") (pinfunction "1_1") (pintype "passive"))
    )
    (net (code "89") (name "Net-(LED1-PadA)") (class "Default")
      (node (ref "LED1") (pin "A") (pinfunction "A_A") (pintype "passive"))
      (node (ref "R7") (pin "1") (pinfunction "1_1") (pintype "passive"))
    )
    (net (code "90") (name "Net-(LED2-PadA)") (class "Default")
      (node (ref "LED2") (pin "A") (pinfunction "A_A") (pintype "passive"))
      (node (ref "R5") (pin "1") (pinfunction "1_1") (pintype "passive"))
    )
    (net (code "91") (name "Net-(LED5-PadA)") (class "Default")
      (node (ref "LED5") (pin "A") (pinfunction "A_A") (pintype "passive"))
      (node (ref "R26") (pin "1") (pinfunction "1_1") (pintype "passive"))
    )
    (net (code "92") (name "Net-(LED6-PadA)") (class "Default")
      (node (ref "LED6") (pin "A") (pinfunction "A_A") (pintype "passive"))
      (node (ref "R27") (pin "1") (pinfunction "1_1") (pintype "passive"))
    )
    (net (code "93") (name "Net-(LED7-PadA)") (class "Default")
      (node (ref "LED7") (pin "A") (pinfunction "A_A") (pintype "passive"))
      (node (ref "R29") (pin "1") (pinfunction "1_1") (pintype "passive"))
    )
    (net (code "94") (name "Net-(LED8-PadA)") (class "Default")
      (node (ref "LED8") (pin "A") (pinfunction "A_A") (pintype "passive"))
      (node (ref "R30") (pin "1") (pinfunction "1_1") (pintype "passive"))
    )
    (net (code "95") (name "Net-(PS1-+VIN)") (class "Default")
      (node (ref "PS1") (pin "1") (pinfunction "+VIN_1") (pintype "bidirectional"))
      (node (ref "PS2") (pin "1") (pinfunction "+VIN_1") (pintype "bidirectional"))
      (node (ref "S3") (pin "1") (pinfunction "1_1") (pintype "bidirectional"))
      (node (ref "S3") (pin "2") (pinfunction "2_2") (pintype "bidirectional"))
    )
    (net (code "96") (name "Net-(Q1-B)") (class "Default")
      (node (ref "C39") (pin "2") (pinfunction "2_2") (pintype "passive"))
      (node (ref "Q1") (pin "3") (pinfunction "B_3") (pintype "bidirectional"))
      (node (ref "R11") (pin "2") (pinfunction "2_2") (pintype "passive"))
      (node (ref "R12") (pin "1") (pinfunction "1_1") (pintype "passive"))
    )
    (net (code "97") (name "Net-(Q2-B)") (class "Default")
      (node (ref "C39") (pin "1") (pinfunction "1_1") (pintype "passive"))
      (node (ref "Q2") (pin "3") (pinfunction "B_3") (pintype "bidirectional"))
      (node (ref "R13") (pin "2") (pinfunction "2_2") (pintype "passive"))
      (node (ref "R14") (pin "1") (pinfunction "1_1") (pintype "passive"))
    )
    (net (code "98") (name "Net-(Q3-B)") (class "Default")
      (node (ref "C40") (pin "2") (pinfunction "2_2") (pintype "passive"))
      (node (ref "Q3") (pin "3") (pinfunction "B_3") (pintype "bidirectional"))
      (node (ref "R18") (pin "2") (pinfunction "2_2") (pintype "passive"))
      (node (ref "R19") (pin "1") (pinfunction "1_1") (pintype "passive"))
    )
    (net (code "99") (name "Net-(Q4-B)") (class "Default")
      (node (ref "C40") (pin "1") (pinfunction "1_1") (pintype "passive"))
      (node (ref "Q4") (pin "3") (pinfunction "B_3") (pintype "bidirectional"))
      (node (ref "R20") (pin "2") (pinfunction "2_2") (pintype "passive"))
      (node (ref "R21") (pin "1") (pinfunction "1_1") (pintype "passive"))
    )
    (net (code "100") (name "Net-(Q8-E)") (class "Default")
      (node (ref "Q8") (pin "2") (pinfunction "E_2") (pintype "bidirectional"))
      (node (ref "R34") (pin "1") (pinfunction "1_1") (pintype "passive"))
    )
    (net (code "101") (name "Net-(S2-K)") (class "Default")
      (node (ref "R34") (pin "2") (pinfunction "2_2") (pintype "passive"))
      (node (ref "S2") (pin "4") (pinfunction "K_4") (pintype "bidirectional"))
    )
    (net (code "102") (name "Net-(U6-GATE)") (class "Default")
      (node (ref "U6") (pin "5") (pinfunction "GATE_5") (pintype "passive"))
      (node (ref "U7") (pin "1") (pinfunction "G_1") (pintype "passive"))
    )
    (net (code "103") (name "OC1") (class "Default")
      (node (ref "IC15") (pin "46") (pinfunction "OC1/QEB1/FLT5/RD0_46") (pintype "bidirectional"))
      (node (ref "IC4") (pin "2") (pinfunction "VF1-_2") (pintype "bidirectional"))
      (node (ref "OC1") (pin "TP") (pinfunction "TP_TP") (pintype "input"))
    )
    (net (code "104") (name "OC1S") (class "Default")
      (node (ref "IC12") (pin "3") (pinfunction "VINA+_3") (pintype "bidirectional"))
      (node (ref "IC9") (pin "12") (pinfunction "P0W_12") (pintype "bidirectional"))
    )
    (net (code "105") (name "OC2") (class "Default")
      (node (ref "IC15") (pin "49") (pinfunction "OC2/SYNCO2/FLT6/RD1_49") (pintype "bidirectional"))
      (node (ref "IC4") (pin "3") (pinfunction "VF2-_3") (pintype "bidirectional"))
      (node (ref "OC2") (pin "TP") (pinfunction "TP_TP") (pintype "input"))
    )
    (net (code "106") (name "OC2S") (class "Default")
      (node (ref "IC12") (pin "5") (pinfunction "VINB+_5") (pintype "bidirectional"))
      (node (ref "IC9") (pin "9") (pinfunction "P1W_9") (pintype "bidirectional"))
    )
    (net (code "107") (name "OC3") (class "Default")
      (node (ref "IC15") (pin "50") (pinfunction "OC3/FLT7/RD2_50") (pintype "bidirectional"))
      (node (ref "IC3") (pin "2") (pinfunction "VF1-_2") (pintype "bidirectional"))
      (node (ref "OC3") (pin "TP") (pinfunction "TP_TP") (pintype "input"))
    )
    (net (code "108") (name "OC3S") (class "Default")
      (node (ref "IC12") (pin "10") (pinfunction "VINC+_10") (pintype "bidirectional"))
      (node (ref "IC9") (pin "19") (pinfunction "P2W_19") (pintype "bidirectional"))
    )
    (net (code "109") (name "OC4") (class "Default")
      (node (ref "IC15") (pin "51") (pinfunction "OC4/SYNCO1/RD3_51") (pintype "bidirectional"))
      (node (ref "IC3") (pin "3") (pinfunction "VF2-_3") (pintype "bidirectional"))
      (node (ref "OC4") (pin "TP") (pinfunction "TP_TP") (pintype "input"))
    )
    (net (code "110") (name "OC4S") (class "Default")
      (node (ref "IC12") (pin "12") (pinfunction "VIND+_12") (pintype "bidirectional"))
      (node (ref "IC9") (pin "2") (pinfunction "P3W_2") (pintype "bidirectional"))
    )
    (net (code "111") (name "PGC_2") (class "Default")
      (node (ref "IC15") (pin "48") (pinfunction "PGEC2/SOSCO/T1CK/CN0/RC14_48") (pintype "bidirectional"))
      (node (ref "J1") (pin "5") (pinfunction "S_5") (pintype "passive"))
    )
    (net (code "112") (name "PGD_2") (class "Default")
      (node (ref "IC15") (pin "47") (pinfunction "PGED2/SOSCI/T4CK/CN1/RC13_47") (pintype "bidirectional"))
      (node (ref "J1") (pin "4") (pinfunction "S_4") (pintype "passive"))
    )
    (net (code "113") (name "PWM2") (class "Default")
      (node (ref "JP4") (pin "3") (pinfunction "3_3") (pintype "passive"))
    )
    (net (code "114") (name "PWM3") (class "Default")
      (node (ref "JP4") (pin "4") (pinfunction "4_4") (pintype "passive"))
    )
    (net (code "115") (name "PWM5") (class "Default")
      (node (ref "JP4") (pin "6") (pinfunction "6_6") (pintype "passive"))
    )
    (net (code "116") (name "PWM6") (class "Default")
      (node (ref "JP4") (pin "7") (pinfunction "7_7") (pintype "passive"))
    )
    (net (code "117") (name "PWM7") (class "Default")
      (node (ref "JP4") (pin "8") (pinfunction "8_8") (pintype "passive"))
    )
    (net (code "118") (name "PWM8") (class "Default")
      (node (ref "JP3") (pin "1") (pinfunction "1_1") (pintype "passive"))
    )
    (net (code "119") (name "PWM11") (class "Default")
      (node (ref "JP3") (pin "4") (pinfunction "4_4") (pintype "passive"))
    )
    (net (code "120") (name "PWM12") (class "Default")
      (node (ref "JP3") (pin "5") (pinfunction "5_5") (pintype "passive"))
    )
    (net (code "121") (name "PWM13") (class "Default")
      (node (ref "JP3") (pin "6") (pinfunction "6_6") (pintype "passive"))
    )
    (net (code "122") (name "RESET~{}") (class "Default")
      (node (ref "IC15") (pin "7") (pinfunction "~{MCLR}_7") (pintype "bidirectional"))
      (node (ref "J1") (pin "1") (pinfunction "S_1") (pintype "passive"))
      (node (ref "R2") (pin "2") (pinfunction "2_2") (pintype "passive"))
    )
    (net (code "123") (name "RX") (class "Default")
      (node (ref "JP4") (pin "1") (pinfunction "1_1") (pintype "passive"))
    )
    (net (code "124") (name "RXD0") (class "Default")
      (node (ref "JP5") (pin "2") (pinfunction "2_2") (pintype "passive"))
    )
    (net (code "125") (name "RXD1") (class "Default")
      (node (ref "JP5") (pin "4") (pinfunction "4_4") (pintype "passive"))
    )
    (net (code "126") (name "RXD2") (class "Default")
      (node (ref "JP5") (pin "6") (pinfunction "6_6") (pintype "passive"))
    )
    (net (code "127") (name "RX_1") (class "Default")
      (node (ref "IC15") (pin "34") (pinfunction "U1RX/SDI1/RF2_34") (pintype "bidirectional"))
      (node (ref "IC2") (pin "1") (pinfunction "TXD_1") (pintype "output"))
      (node (ref "RX") (pin "TP") (pinfunction "TP_TP") (pintype "input"))
    )
    (net (code "128") (name "SCK2") (class "Default")
      (node (ref "IC11") (pin "5") (pinfunction "CATHODE2_5") (pintype "bidirectional"))
      (node (ref "IC15") (pin "4") (pinfunction "SCK2/FLT12/CN8/RG6_4") (pintype "bidirectional"))
      (node (ref "SCK") (pin "TP") (pinfunction "TP_TP") (pintype "input"))
    )
    (net (code "129") (name "SCK_ISO") (class "Default")
      (node (ref "IC11") (pin "12") (pinfunction "V02_12") (pintype "bidirectional"))
      (node (ref "IC9") (pin "5") (pinfunction "SCK_5") (pintype "bidirectional"))
      (node (ref "RN1") (pin "5") (pinfunction "R3_1_5") (pintype "bidirectional"))
    )
    (net (code "130") (name "SCL0-3") (class "Default")
      (node (ref "JP5") (pin "8") (pinfunction "8_8") (pintype "passive"))
    )
    (net (code "131") (name "SCL1") (class "Default")
      (node (ref "IC15") (pin "37") (pinfunction "SCL1/RG2_37") (pintype "bidirectional"))
      (node (ref "JP3") (pin "10") (pinfunction "10_10") (pintype "passive"))
      (node (ref "R4") (pin "2") (pinfunction "2_2") (pintype "passive"))
    )
    (net (code "132") (name "SDA0-3") (class "Default")
      (node (ref "JP5") (pin "7") (pinfunction "7_7") (pintype "passive"))
    )
    (net (code "133") (name "SDA1") (class "Default")
      (node (ref "IC15") (pin "36") (pinfunction "SDA1/RG3_36") (pintype "bidirectional"))
      (node (ref "JP3") (pin "9") (pinfunction "9_9") (pintype "passive"))
      (node (ref "R3") (pin "2") (pinfunction "2_2") (pintype "passive"))
    )
    (net (code "134") (name "SDI2") (class "Default")
      (node (ref "IC11") (pin "2") (pinfunction "V04_2") (pintype "bidirectional"))
      (node (ref "IC15") (pin "5") (pinfunction "SDI2/FLT11/CN9/RG7_5") (pintype "bidirectional"))
      (node (ref "RN1") (pin "1") (pinfunction "R1_1_1") (pintype "bidirectional"))
      (node (ref "SDI") (pin "TP") (pinfunction "TP_TP") (pintype "input"))
    )
    (net (code "135") (name "SDI_ISO") (class "Default")
      (node (ref "IC11") (pin "16") (pinfunction "CATHODE4_16") (pintype "bidirectional"))
      (node (ref "IC9") (pin "16") (pinfunction "SDO_16") (pintype "bidirectional"))
    )
    (net (code "136") (name "SDO2") (class "Default")
      (node (ref "IC11") (pin "7") (pinfunction "CATHODE3_7") (pintype "bidirectional"))
      (node (ref "IC15") (pin "6") (pinfunction "SDO2/FLT10/CN10/RG8_6") (pintype "bidirectional"))
      (node (ref "SDO") (pin "TP") (pinfunction "TP_TP") (pintype "input"))
    )
    (net (code "137") (name "SDO_ISO") (class "Default")
      (node (ref "IC11") (pin "11") (pinfunction "V03_11") (pintype "bidirectional"))
      (node (ref "IC9") (pin "6") (pinfunction "SDI_6") (pintype "bidirectional"))
      (node (ref "RN1") (pin "7") (pinfunction "R4_1_7") (pintype "bidirectional"))
    )
    (net (code "138") (name "SS1{slash}PWM4") (class "Default")
      (node (ref "JP4") (pin "5") (pinfunction "5_5") (pintype "passive"))
    )
    (net (code "139") (name "STIM1_LED") (class "Default")
      (node (ref "IC15") (pin "16") (pinfunction "PGED3/AN0/CMP1A/CMP4C/CN2/RB0_16") (pintype "bidirectional"))
      (node (ref "R29") (pin "2") (pinfunction "2_2") (pintype "passive"))
    )
    (net (code "140") (name "STIM2_LED") (class "Default")
      (node (ref "IC15") (pin "17") (pinfunction "PGEC1/AN6/CMP3C/CMP4A/OCFA/RB6_17") (pintype "bidirectional"))
      (node (ref "R30") (pin "2") (pinfunction "2_2") (pintype "passive"))
    )
    (net (code "141") (name "SUPPLY_STATUS") (class "Default")
      (node (ref "IC15") (pin "45") (pinfunction "IC4/QEA1/FLT4/INT4/RD11_45") (pintype "bidirectional"))
      (node (ref "R33") (pin "2") (pinfunction "2_2") (pintype "passive"))
      (node (ref "U6") (pin "4") (pinfunction "STAT_4") (pintype "output"))
    )
    (net (code "142") (name "TX") (class "Default")
      (node (ref "JP4") (pin "2") (pinfunction "2_2") (pintype "passive"))
    )
    (net (code "143") (name "TXD0") (class "Default")
      (node (ref "JP5") (pin "1") (pinfunction "1_1") (pintype "passive"))
    )
    (net (code "144") (name "TXD1") (class "Default")
      (node (ref "JP5") (pin "3") (pinfunction "3_3") (pintype "passive"))
    )
    (net (code "145") (name "TXD2") (class "Default")
      (node (ref "JP5") (pin "5") (pinfunction "5_5") (pintype "passive"))
    )
    (net (code "146") (name "TX_1") (class "Default")
      (node (ref "IC15") (pin "33") (pinfunction "U1TX/SDO1/RF3_33") (pintype "bidirectional"))
      (node (ref "IC2") (pin "5") (pinfunction "RXD_5") (pintype "input"))
      (node (ref "TX") (pin "TP") (pinfunction "TP_TP") (pintype "input"))
    )
    (net (code "147") (name "USB_5V") (class "Default")
      (node (ref "C6") (pin "1") (pinfunction "1_1") (pintype "passive"))
      (node (ref "D4") (pin "2") (pinfunction "A_2") (pintype "bidirectional"))
      (node (ref "F1") (pin "1") (pinfunction "1_1") (pintype "passive"))
      (node (ref "IC2") (pin "20") (pinfunction "VCC_20") (pintype "power_in"))
      (node (ref "R5") (pin "2") (pinfunction "2_2") (pintype "passive"))
      (node (ref "R6") (pin "2") (pinfunction "2_2") (pintype "passive"))
      (node (ref "R7") (pin "2") (pinfunction "2_2") (pintype "passive"))
    )
    (net (code "148") (name "VCC") (class "Default")
      (node (ref "+HV") (pin "TP") (pinfunction "TP_TP") (pintype "input"))
      (node (ref "C32") (pin "1") (pinfunction "1_1") (pintype "passive"))
      (node (ref "C35") (pin "1") (pinfunction "1_1") (pintype "passive"))
      (node (ref "C37") (pin "1") (pinfunction "1_1") (pintype "passive"))
      (node (ref "PS2") (pin "5") (pinfunction "+VOUT_5") (pintype "bidirectional"))
      (node (ref "Q2") (pin "2") (pinfunction "C_2") (pintype "bidirectional"))
      (node (ref "Q4") (pin "2") (pinfunction "C_2") (pintype "bidirectional"))
      (node (ref "R14") (pin "2") (pinfunction "2_2") (pintype "passive"))
      (node (ref "R21") (pin "2") (pinfunction "2_2") (pintype "passive"))
    )
    (net (code "149") (name "VIN") (class "Default")
      (node (ref "C26") (pin "1") (pinfunction "1_1") (pintype "passive"))
      (node (ref "D2") (pin "P$1") (pinfunction "K_P$1") (pintype "bidirectional"))
      (node (ref "D3") (pin "K") (pinfunction "C_K") (pintype "passive"))
      (node (ref "IC14") (pin "1") (pinfunction "EN_1") (pintype "bidirectional"))
      (node (ref "IC14") (pin "2") (pinfunction "IN_2") (pintype "bidirectional"))
      (node (ref "JP6") (pin "8") (pinfunction "8_8") (pintype "passive"))
    )
    (net (code "150") (name "VIN+") (class "Default")
      (node (ref "J7") (pin "1") (pinfunction "1_1") (pintype "bidirectional"))
      (node (ref "L1") (pin "2") (pinfunction "2_2") (pintype "passive"))
    )
    (net (code "151") (name "VIN_5V") (class "Default")
      (node (ref "C25") (pin "1") (pinfunction "1_1") (pintype "passive"))
      (node (ref "C29") (pin "+") (pinfunction "+_+") (pintype "passive"))
      (node (ref "C30") (pin "1") (pinfunction "+_1") (pintype "bidirectional"))
      (node (ref "D4") (pin "1") (pinfunction "K_1") (pintype "bidirectional"))
      (node (ref "D5") (pin "1") (pinfunction "K_1") (pintype "bidirectional"))
      (node (ref "IC13") (pin "1") (pinfunction "IN_1") (pintype "bidirectional"))
      (node (ref "IC13") (pin "3") (pinfunction "EN_3") (pintype "bidirectional"))
      (node (ref "PS3") (pin "2") (pinfunction "+VIN_(VCC)_2") (pintype "bidirectional"))
      (node (ref "R33") (pin "1") (pinfunction "1_1") (pintype "passive"))
      (node (ref "S3") (pin "3") (pinfunction "3_3") (pintype "bidirectional"))
      (node (ref "U6") (pin "6") (pinfunction "SENSE_6") (pintype "input"))
      (node (ref "U7") (pin "2") (pinfunction "S_2") (pintype "passive"))
      (node (ref "VIN5V") (pin "TP") (pinfunction "TP_TP") (pintype "input"))
    )
    (net (code "152") (name "VSS") (class "Default")
      (node (ref "-HV") (pin "TP") (pinfunction "TP_TP") (pintype "input"))
      (node (ref "C31") (pin "2") (pinfunction "2_2") (pintype "passive"))
      (node (ref "C36") (pin "1") (pinfunction "1_1") (pintype "passive"))
      (node (ref "C38") (pin "1") (pinfunction "1_1") (pintype "passive"))
      (node (ref "PS1") (pin "8") (pinfunction "-VOUT3_8") (pintype "bidirectional"))
      (node (ref "Q1") (pin "2") (pinfunction "C_2") (pintype "bidirectional"))
      (node (ref "Q3") (pin "2") (pinfunction "C_2") (pintype "bidirectional"))
      (node (ref "R11") (pin "1") (pinfunction "1_1") (pintype "passive"))
      (node (ref "R18") (pin "1") (pinfunction "1_1") (pintype "passive"))
    )
    (net (code "153") (name "VSTIM1N") (class "Default")
      (node (ref "IC12") (pin "6") (pinfunction "VINB-_6") (pintype "bidirectional"))
      (node (ref "IC12") (pin "7") (pinfunction "VOUTB_7") (pintype "bidirectional"))
      (node (ref "IC5") (pin "2") (pinfunction "-IN_2") (pintype "input"))
      (node (ref "VSTIM1N") (pin "TP") (pinfunction "TP_TP") (pintype "input"))
    )
    (net (code "154") (name "VSTIM1P") (class "Default")
      (node (ref "IC12") (pin "1") (pinfunction "VOUTA_1") (pintype "bidirectional"))
      (node (ref "IC12") (pin "2") (pinfunction "VINA-_2") (pintype "bidirectional"))
      (node (ref "IC5") (pin "3") (pinfunction "+IN_3") (pintype "input"))
      (node (ref "VSTIM1P") (pin "TP") (pinfunction "TP_TP") (pintype "input"))
    )
    (net (code "155") (name "VSTIM2N") (class "Default")
      (node (ref "IC12") (pin "13") (pinfunction "VIND-_13") (pintype "bidirectional"))
      (node (ref "IC12") (pin "14") (pinfunction "V_OUTD_14") (pintype "bidirectional"))
      (node (ref "IC8") (pin "2") (pinfunction "-IN_2") (pintype "input"))
      (node (ref "VSTIM2N") (pin "TP") (pinfunction "TP_TP") (pintype "input"))
    )
    (net (code "156") (name "VSTIM2P") (class "Default")
      (node (ref "IC12") (pin "8") (pinfunction "V_OUTC_8") (pintype "bidirectional"))
      (node (ref "IC12") (pin "9") (pinfunction "VINC-_9") (pintype "bidirectional"))
      (node (ref "IC8") (pin "3") (pinfunction "+IN_3") (pintype "input"))
      (node (ref "VSTIM2P") (pin "TP") (pinfunction "TP_TP") (pintype "input"))
    )
    (net (code "157") (name "XVCC") (class "Default")
      (node (ref "F1") (pin "2") (pinfunction "2_2") (pintype "passive"))
      (node (ref "J2") (pin "1") (pinfunction "VBUS_1") (pintype "bidirectional"))
      (node (ref "TP3") (pin "X") (pinfunction "P$1_X") (pintype "passive"))
    )
    (net (code "158") (name "unconnected-(IC2-CBUS2-Pad13)") (class "Default")
      (node (ref "IC2") (pin "13") (pinfunction "CBUS2_13") (pintype "bidirectional"))
    )
    (net (code "159") (name "unconnected-(IC2-CBUS4-Pad12)") (class "Default")
      (node (ref "IC2") (pin "12") (pinfunction "CBUS4_12") (pintype "bidirectional"))
    )
    (net (code "160") (name "unconnected-(IC2-OSCI-Pad27)") (class "Default")
      (node (ref "IC2") (pin "27") (pinfunction "OSCI_27") (pintype "input"))
    )
    (net (code "161") (name "unconnected-(IC2-OSCO-Pad28)") (class "Default")
      (node (ref "IC2") (pin "28") (pinfunction "OSCO_28") (pintype "output"))
    )
    (net (code "162") (name "unconnected-(IC2-~{CTS}-Pad11)") (class "Default")
      (node (ref "IC2") (pin "11") (pinfunction "~{CTS}_11") (pintype "input"))
    )
    (net (code "163") (name "unconnected-(IC2-~{DCD}-Pad10)") (class "Default")
      (node (ref "IC2") (pin "10") (pinfunction "~{DCD}_10") (pintype "input"))
    )
    (net (code "164") (name "unconnected-(IC2-~{DSR}-Pad9)") (class "Default")
      (node (ref "IC2") (pin "9") (pinfunction "~{DSR}_9") (pintype "input"))
    )
    (net (code "165") (name "unconnected-(IC2-~{DTR}-Pad2)") (class "Default")
      (node (ref "IC2") (pin "2") (pinfunction "~{DTR}_2") (pintype "output"))
    )
    (net (code "166") (name "unconnected-(IC2-~{RESET}-Pad19)") (class "Default")
      (node (ref "IC2") (pin "19") (pinfunction "~{RESET}_19") (pintype "input"))
    )
    (net (code "167") (name "unconnected-(IC2-~{RI}-Pad6)") (class "Default")
      (node (ref "IC2") (pin "6") (pinfunction "~{RI}_6") (pintype "input"))
    )
    (net (code "168") (name "unconnected-(IC2-~{RTS}-Pad3)") (class "Default")
      (node (ref "IC2") (pin "3") (pinfunction "~{RTS}_3") (pintype "output"))
    )
    (net (code "169") (name "unconnected-(IC5-NC-Pad8)") (class "Default")
      (node (ref "IC5") (pin "8") (pinfunction "NC_8") (pintype "no_connect"))
    )
    (net (code "170") (name "unconnected-(IC7-NC-Pad1)") (class "Default")
      (node (ref "IC7") (pin "1") (pinfunction "NC_1") (pintype "no_connect"))
    )
    (net (code "171") (name "unconnected-(IC7-NC_1-Pad5)") (class "Default")
      (node (ref "IC7") (pin "5") (pinfunction "NC_1_5") (pintype "bidirectional"))
    )
    (net (code "172") (name "unconnected-(IC7-NC_2-Pad8)") (class "Default")
      (node (ref "IC7") (pin "8") (pinfunction "NC_2_8") (pintype "bidirectional"))
    )
    (net (code "173") (name "unconnected-(IC8-NC-Pad8)") (class "Default")
      (node (ref "IC8") (pin "8") (pinfunction "NC_8") (pintype "no_connect"))
    )
    (net (code "174") (name "unconnected-(IC10-NC-Pad1)") (class "Default")
      (node (ref "IC10") (pin "1") (pinfunction "NC_1") (pintype "no_connect"))
    )
    (net (code "175") (name "unconnected-(IC10-NC_1-Pad5)") (class "Default")
      (node (ref "IC10") (pin "5") (pinfunction "NC_1_5") (pintype "bidirectional"))
    )
    (net (code "176") (name "unconnected-(IC10-NC_2-Pad8)") (class "Default")
      (node (ref "IC10") (pin "8") (pinfunction "NC_2_8") (pintype "bidirectional"))
    )
    (net (code "177") (name "unconnected-(IC15-AN3{slash}CMP2B{slash}AINDX1{slash}CN5{slash}RB3-Pad13)") (class "Default")
      (node (ref "IC15") (pin "13") (pinfunction "AN3/CMP2B/AINDX1/CN5/RB3_13") (pintype "bidirectional"))
    )
    (net (code "178") (name "unconnected-(IC15-AN4{slash}CMP2C{slash}CMP3A{slash}AQEA1{slash}CN6{slash}RB4-Pad12)") (class "Default")
      (node (ref "IC15") (pin "12") (pinfunction "AN4/CMP2C/CMP3A/AQEA1/CN6/RB4_12") (pintype "bidirectional"))
    )
    (net (code "179") (name "unconnected-(IC15-AN5{slash}CMP3B{slash}AQEB1{slash}CN7{slash}RB5-Pad11)") (class "Default")
      (node (ref "IC15") (pin "11") (pinfunction "AN5/CMP3B/AQEB1/CN7/RB5_11") (pintype "bidirectional"))
    )
    (net (code "180") (name "unconnected-(IC15-AN8{slash}~{U2CTS}{slash}RB8-Pad21)") (class "Default")
      (node (ref "IC15") (pin "21") (pinfunction "AN8/~{U2CTS}/RB8_21") (pintype "bidirectional"))
    )
    (net (code "181") (name "unconnected-(IC15-C1TX{slash}RF1-Pad59)") (class "Default")
      (node (ref "IC15") (pin "59") (pinfunction "C1TX/RF1_59") (pintype "bidirectional"))
    )
    (net (code "182") (name "unconnected-(IC15-OSC1{slash}CLKIN{slash}RC12-Pad39)") (class "Default")
      (node (ref "IC15") (pin "39") (pinfunction "OSC1/CLKIN/RC12_39") (pintype "bidirectional"))
    )
    (net (code "183") (name "unconnected-(IC15-OSC2{slash}REFCLKO{slash}CLKO{slash}RC15-Pad40)") (class "Default")
      (node (ref "IC15") (pin "40") (pinfunction "OSC2/REFCLKO/CLKO/RC15_40") (pintype "bidirectional"))
    )
    (net (code "184") (name "unconnected-(IC15-PWM1H{slash}RE1-Pad61)") (class "Default")
      (node (ref "IC15") (pin "61") (pinfunction "PWM1H/RE1_61") (pintype "bidirectional"))
    )
    (net (code "185") (name "unconnected-(IC15-PWM2H{slash}RE3-Pad63)") (class "Default")
      (node (ref "IC15") (pin "63") (pinfunction "PWM2H/RE3_63") (pintype "bidirectional"))
    )
    (net (code "186") (name "unconnected-(IC15-PWM3H{slash}RE5-Pad1)") (class "Default")
      (node (ref "IC15") (pin "1") (pinfunction "PWM3H/RE5_1") (pintype "bidirectional"))
    )
    (net (code "187") (name "unconnected-(IC15-PWM4H{slash}RE7-Pad3)") (class "Default")
      (node (ref "IC15") (pin "3") (pinfunction "PWM4H/RE7_3") (pintype "bidirectional"))
    )
    (net (code "188") (name "unconnected-(IC15-PWM4L{slash}RE6-Pad2)") (class "Default")
      (node (ref "IC15") (pin "2") (pinfunction "PWM4L/RE6_2") (pintype "bidirectional"))
    )
    (net (code "189") (name "unconnected-(IC15-PWM5H{slash}UPDN1{slash}CN16{slash}RD7-Pad55)") (class "Default")
      (node (ref "IC15") (pin "55") (pinfunction "PWM5H/UPDN1/CN16/RD7_55") (pintype "bidirectional"))
    )
    (net (code "190") (name "unconnected-(IC15-PWM5L{slash}CN15{slash}RD6-Pad54)") (class "Default")
      (node (ref "IC15") (pin "54") (pinfunction "PWM5L/CN15/RD6_54") (pintype "bidirectional"))
    )
    (net (code "191") (name "unconnected-(IC15-TDO{slash}AN11{slash}EXTREF{slash}RB11-Pad24)") (class "Default")
      (node (ref "IC15") (pin "24") (pinfunction "TDO/AN11/EXTREF/RB11_24") (pintype "bidirectional"))
    )
    (net (code "192") (name "unconnected-(IC15-TMS{slash}AN10{slash}INDX2{slash}RB10-Pad23)") (class "Default")
      (node (ref "IC15") (pin "23") (pinfunction "TMS/AN10/INDX2/RB10_23") (pintype "bidirectional"))
    )
    (net (code "193") (name "unconnected-(J2-ID-Pad4)") (class "Default")
      (node (ref "J2") (pin "4") (pinfunction "ID_4") (pintype "bidirectional"))
    )
    (net (code "194") (name "unconnected-(JP6-Pad1)") (class "Default")
      (node (ref "JP6") (pin "1") (pinfunction "1_1") (pintype "passive"))
    )
    (net (code "195") (name "unconnected-(JP6-Pad2)") (class "Default")
      (node (ref "JP6") (pin "2") (pinfunction "2_2") (pintype "passive"))
    )
    (net (code "196") (name "unconnected-(JP6-Pad4)") (class "Default")
      (node (ref "JP6") (pin "4") (pinfunction "4_4") (pintype "passive"))
    )
    (net (code "197") (name "unconnected-(JP7-Pad2)") (class "Default")
      (node (ref "JP7") (pin "2") (pinfunction "2_2") (pintype "passive"))
    )
    (net (code "198") (name "unconnected-(JP7-Pad3)") (class "Default")
      (node (ref "JP7") (pin "3") (pinfunction "3_3") (pintype "passive"))
    )
    (net (code "199") (name "unconnected-(PS1--VOUT1-Pad6)") (class "Default")
      (node (ref "PS1") (pin "6") (pinfunction "-VOUT1_6") (pintype "bidirectional"))
    )
    (net (code "200") (name "unconnected-(PS1--VOUT2-Pad7)") (class "Default")
      (node (ref "PS1") (pin "7") (pinfunction "-VOUT2_7") (pintype "bidirectional"))
    )
    (net (code "201") (name "unconnected-(PS2--VOUT1-Pad6)") (class "Default")
      (node (ref "PS2") (pin "6") (pinfunction "-VOUT1_6") (pintype "bidirectional"))
    )
    (net (code "202") (name "unconnected-(PS2--VOUT2-Pad7)") (class "Default")
      (node (ref "PS2") (pin "7") (pinfunction "-VOUT2_7") (pintype "bidirectional"))
    )
  )
)
